# mcat-4cu-b-v2g.net
KiCad netlist of a schematic drawn in EAGLE
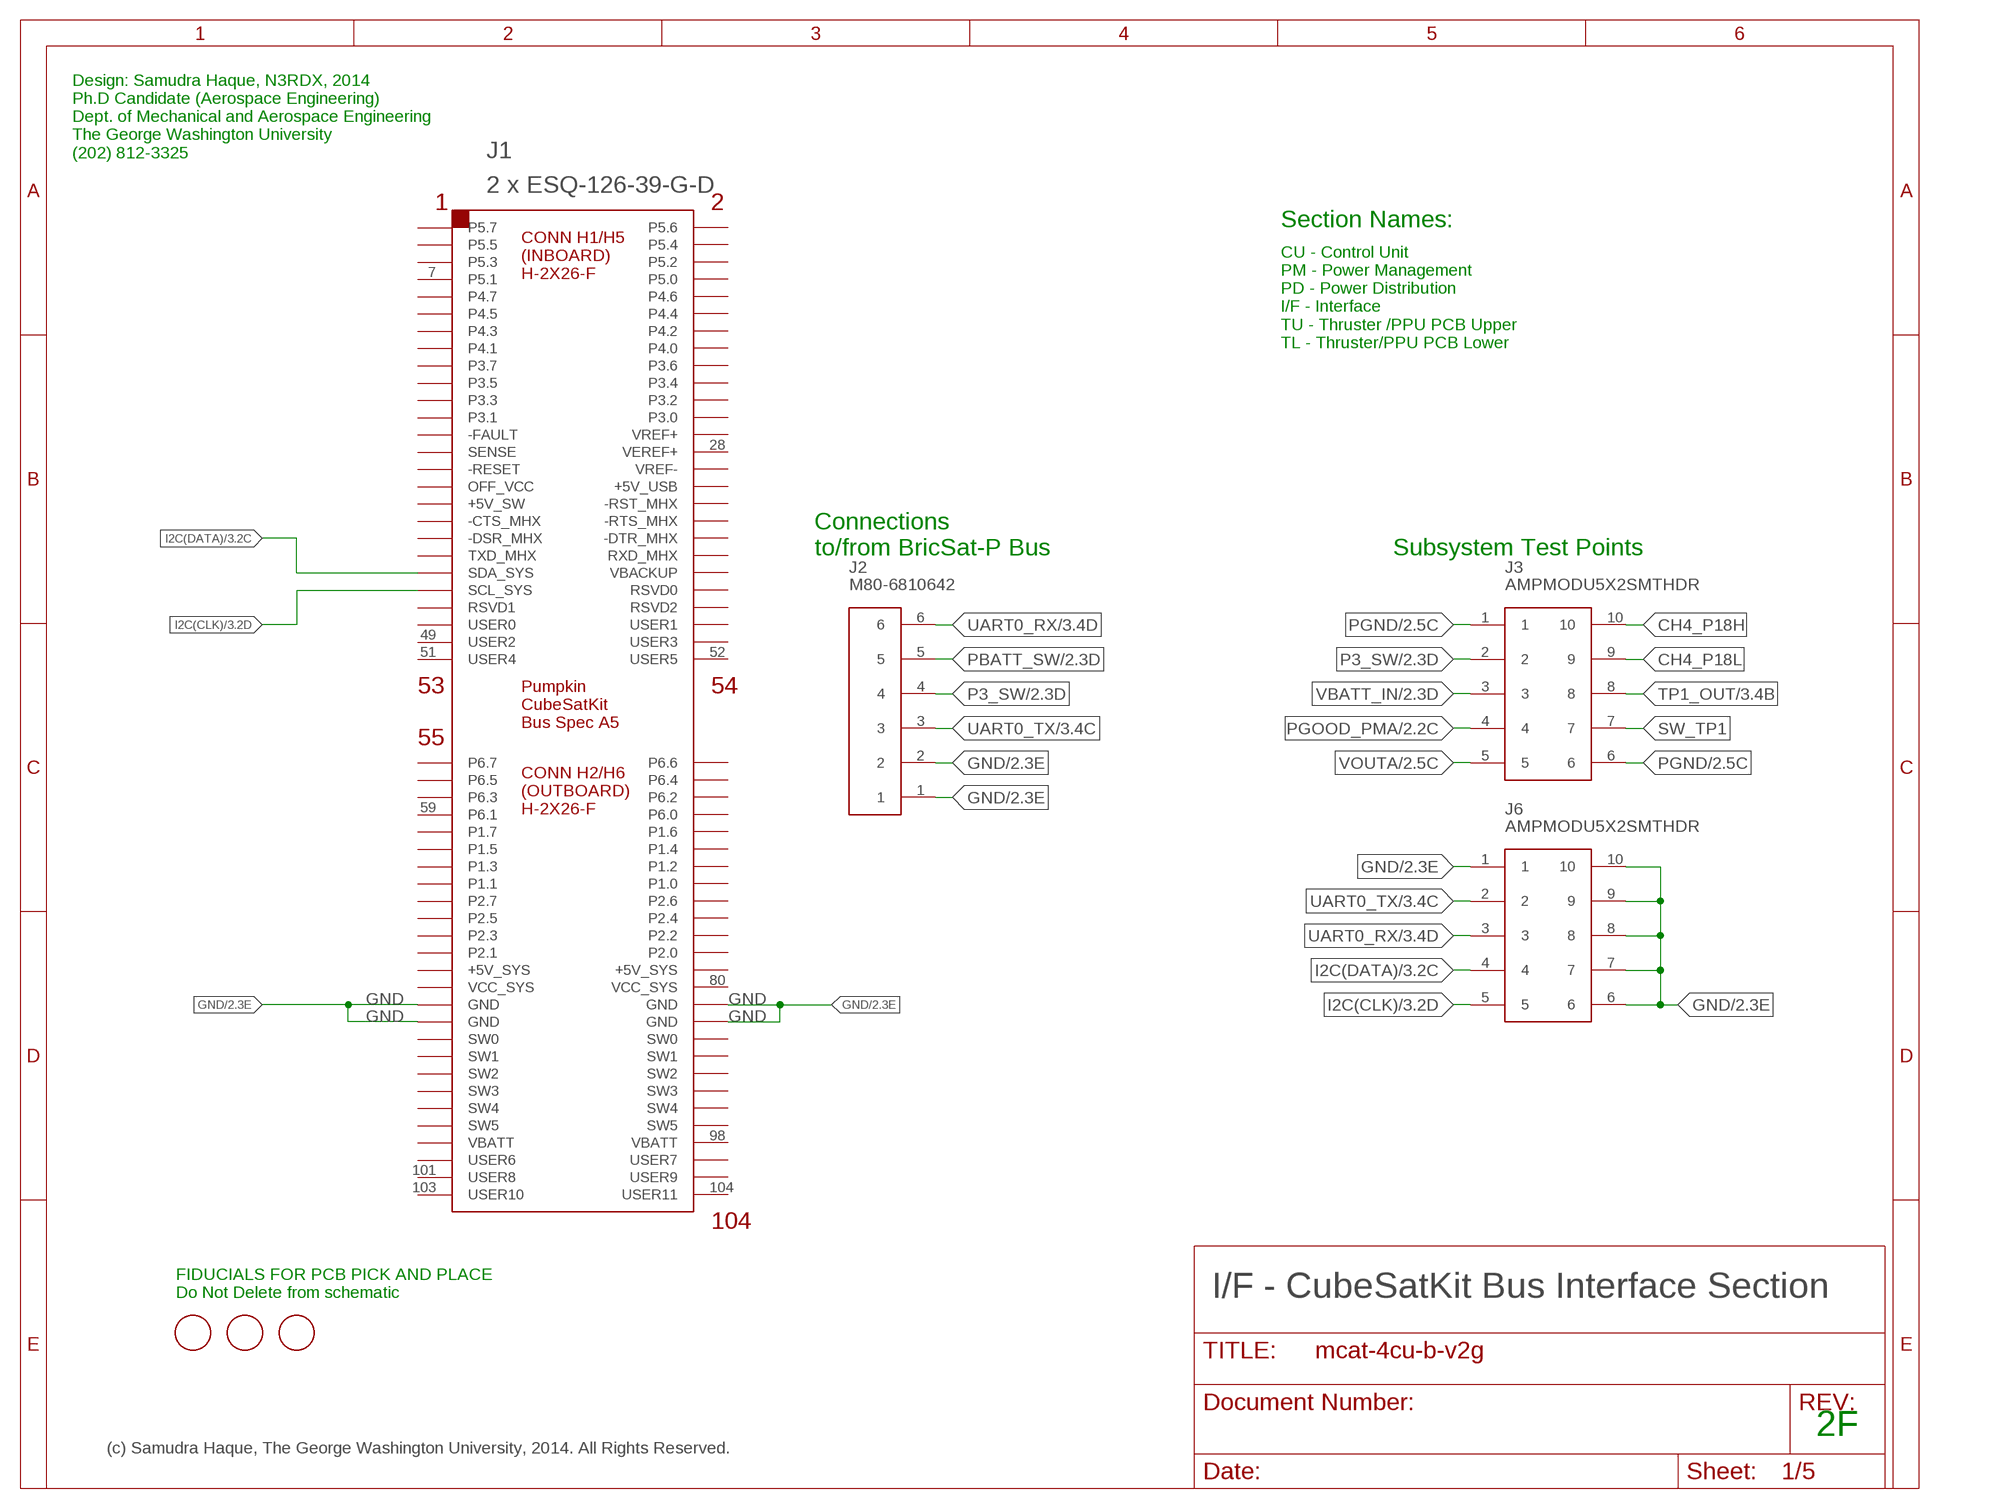
[diagram p0: schematic, sheet 1]
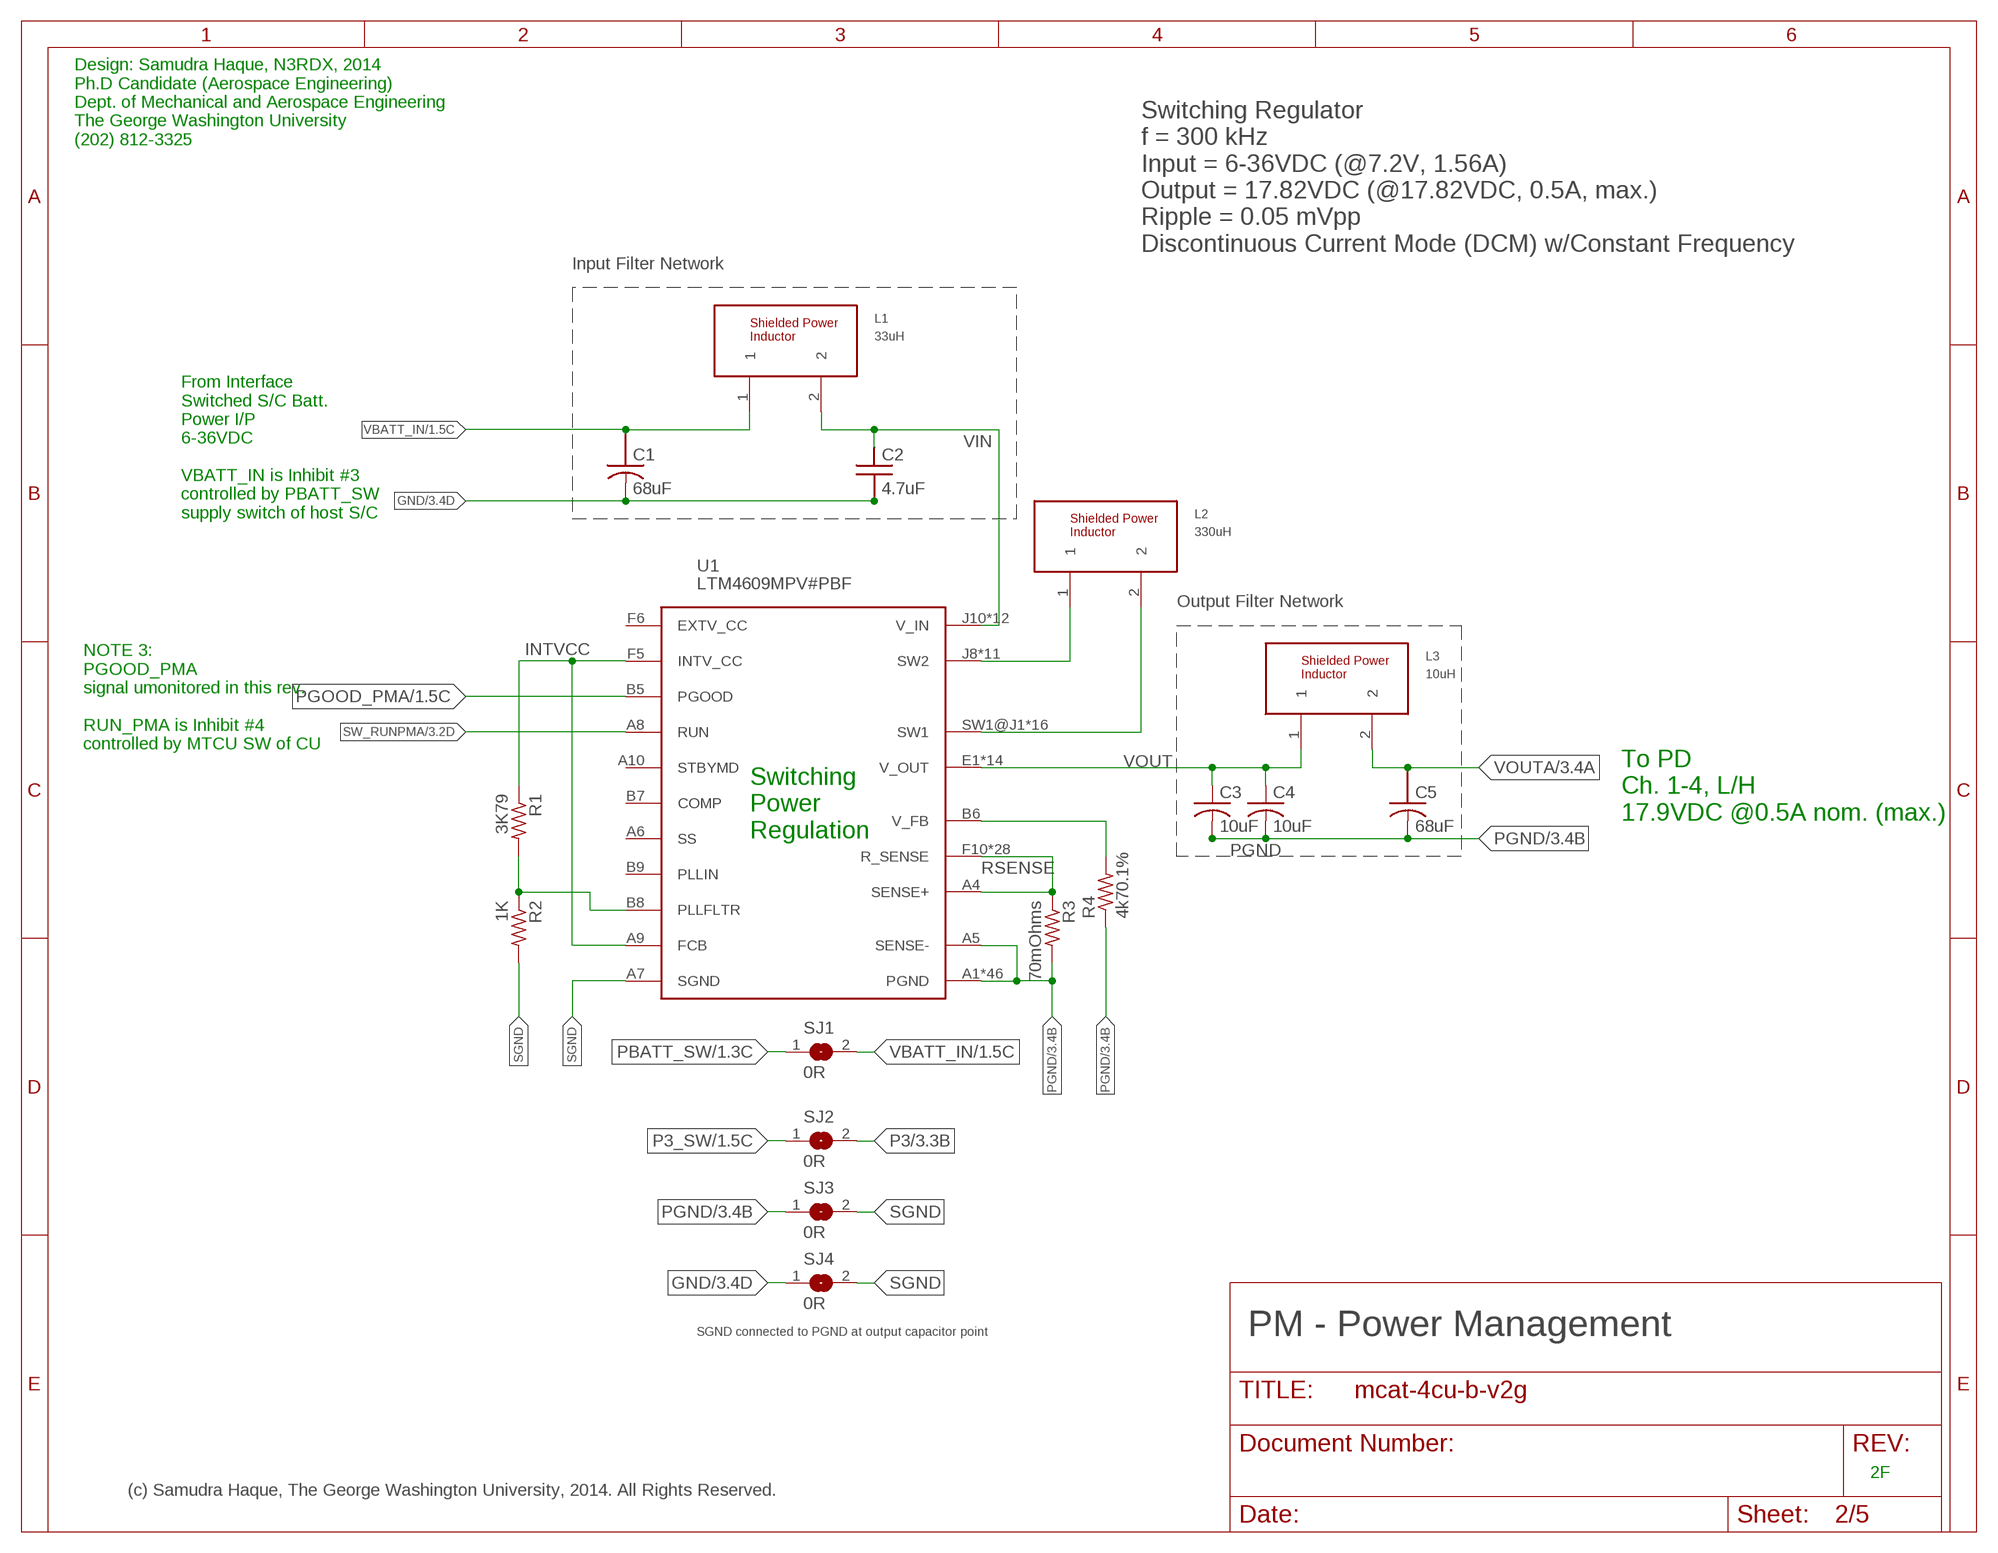
[diagram p1: schematic, sheet 2]
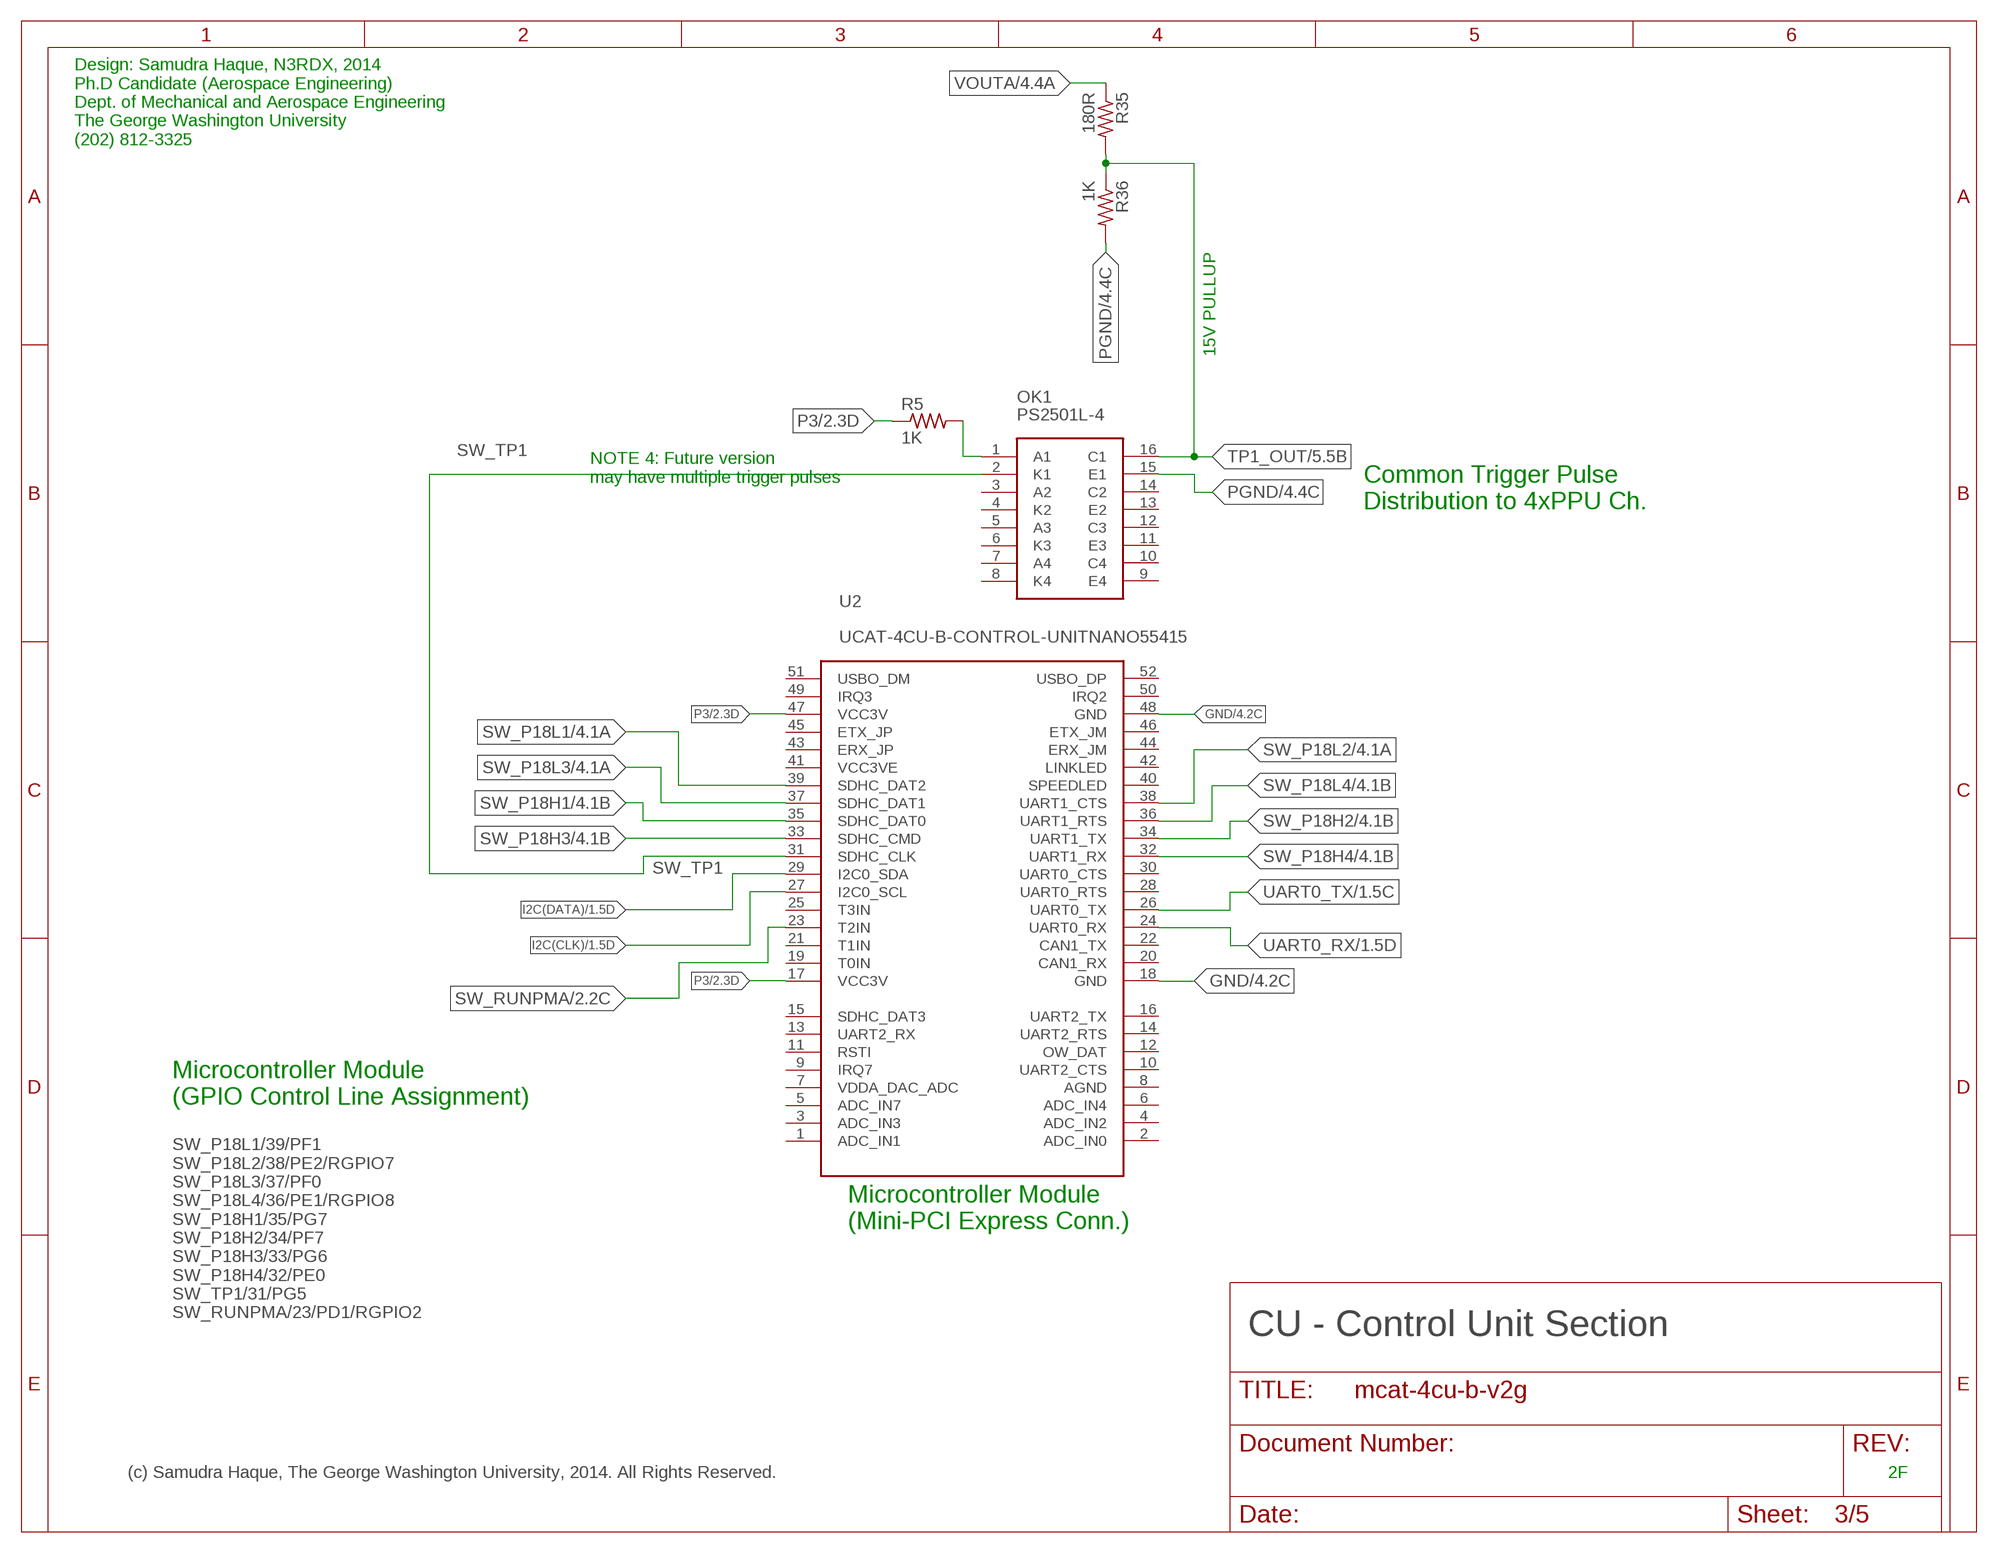
[diagram p2: schematic, sheet 3]
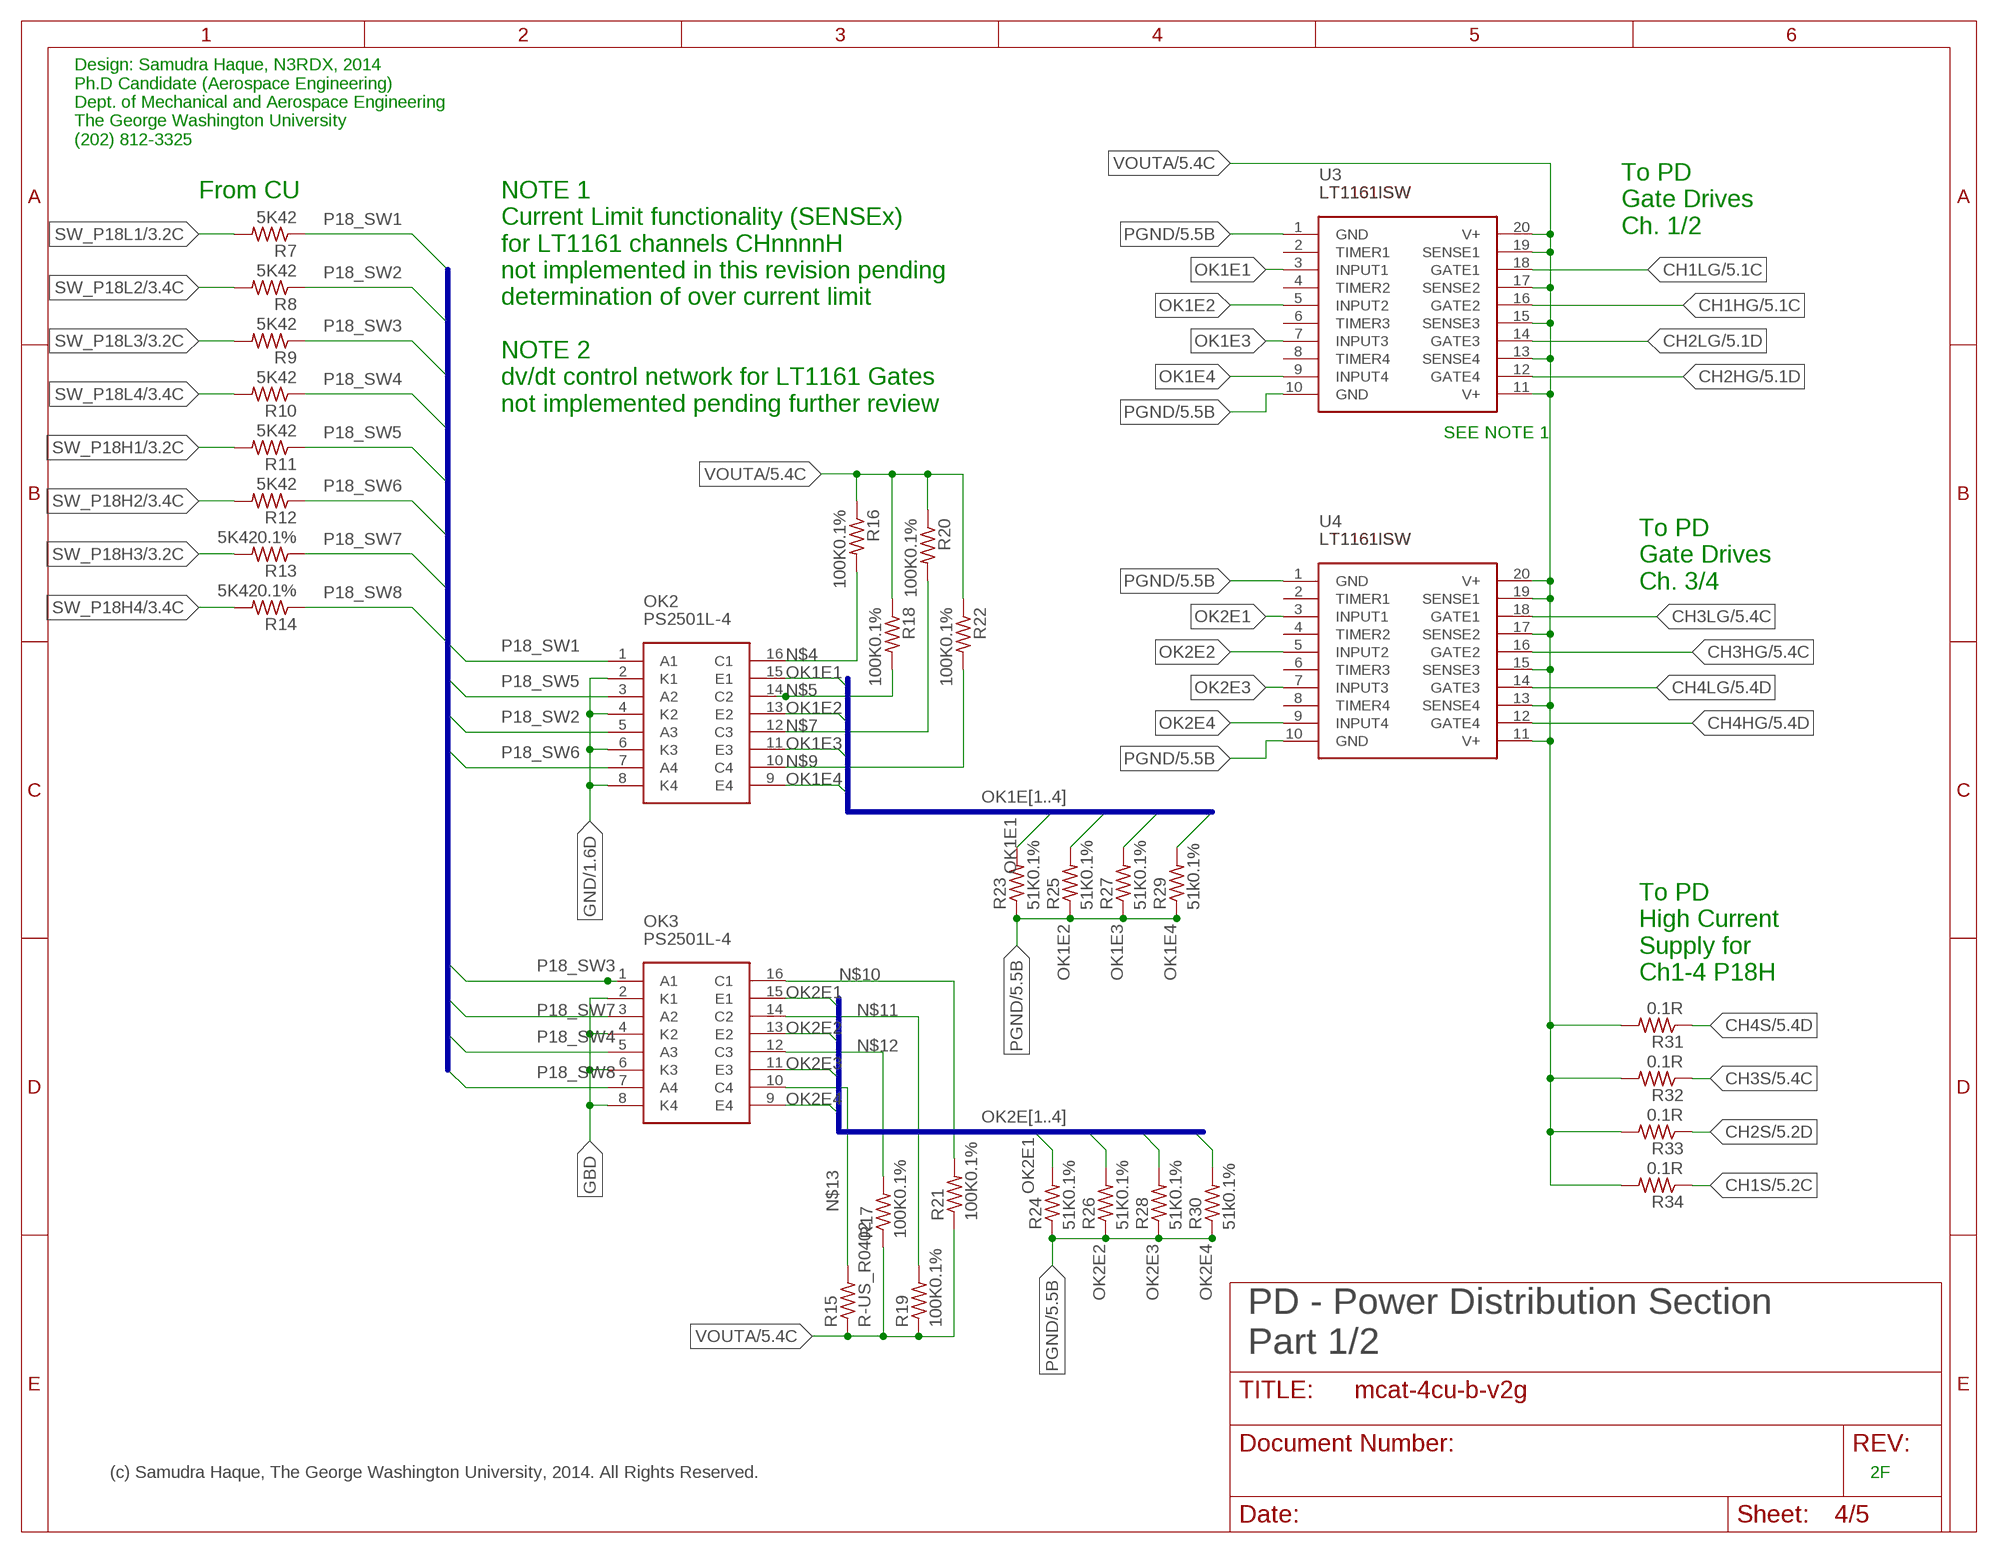
[diagram p3: schematic, sheet 4]
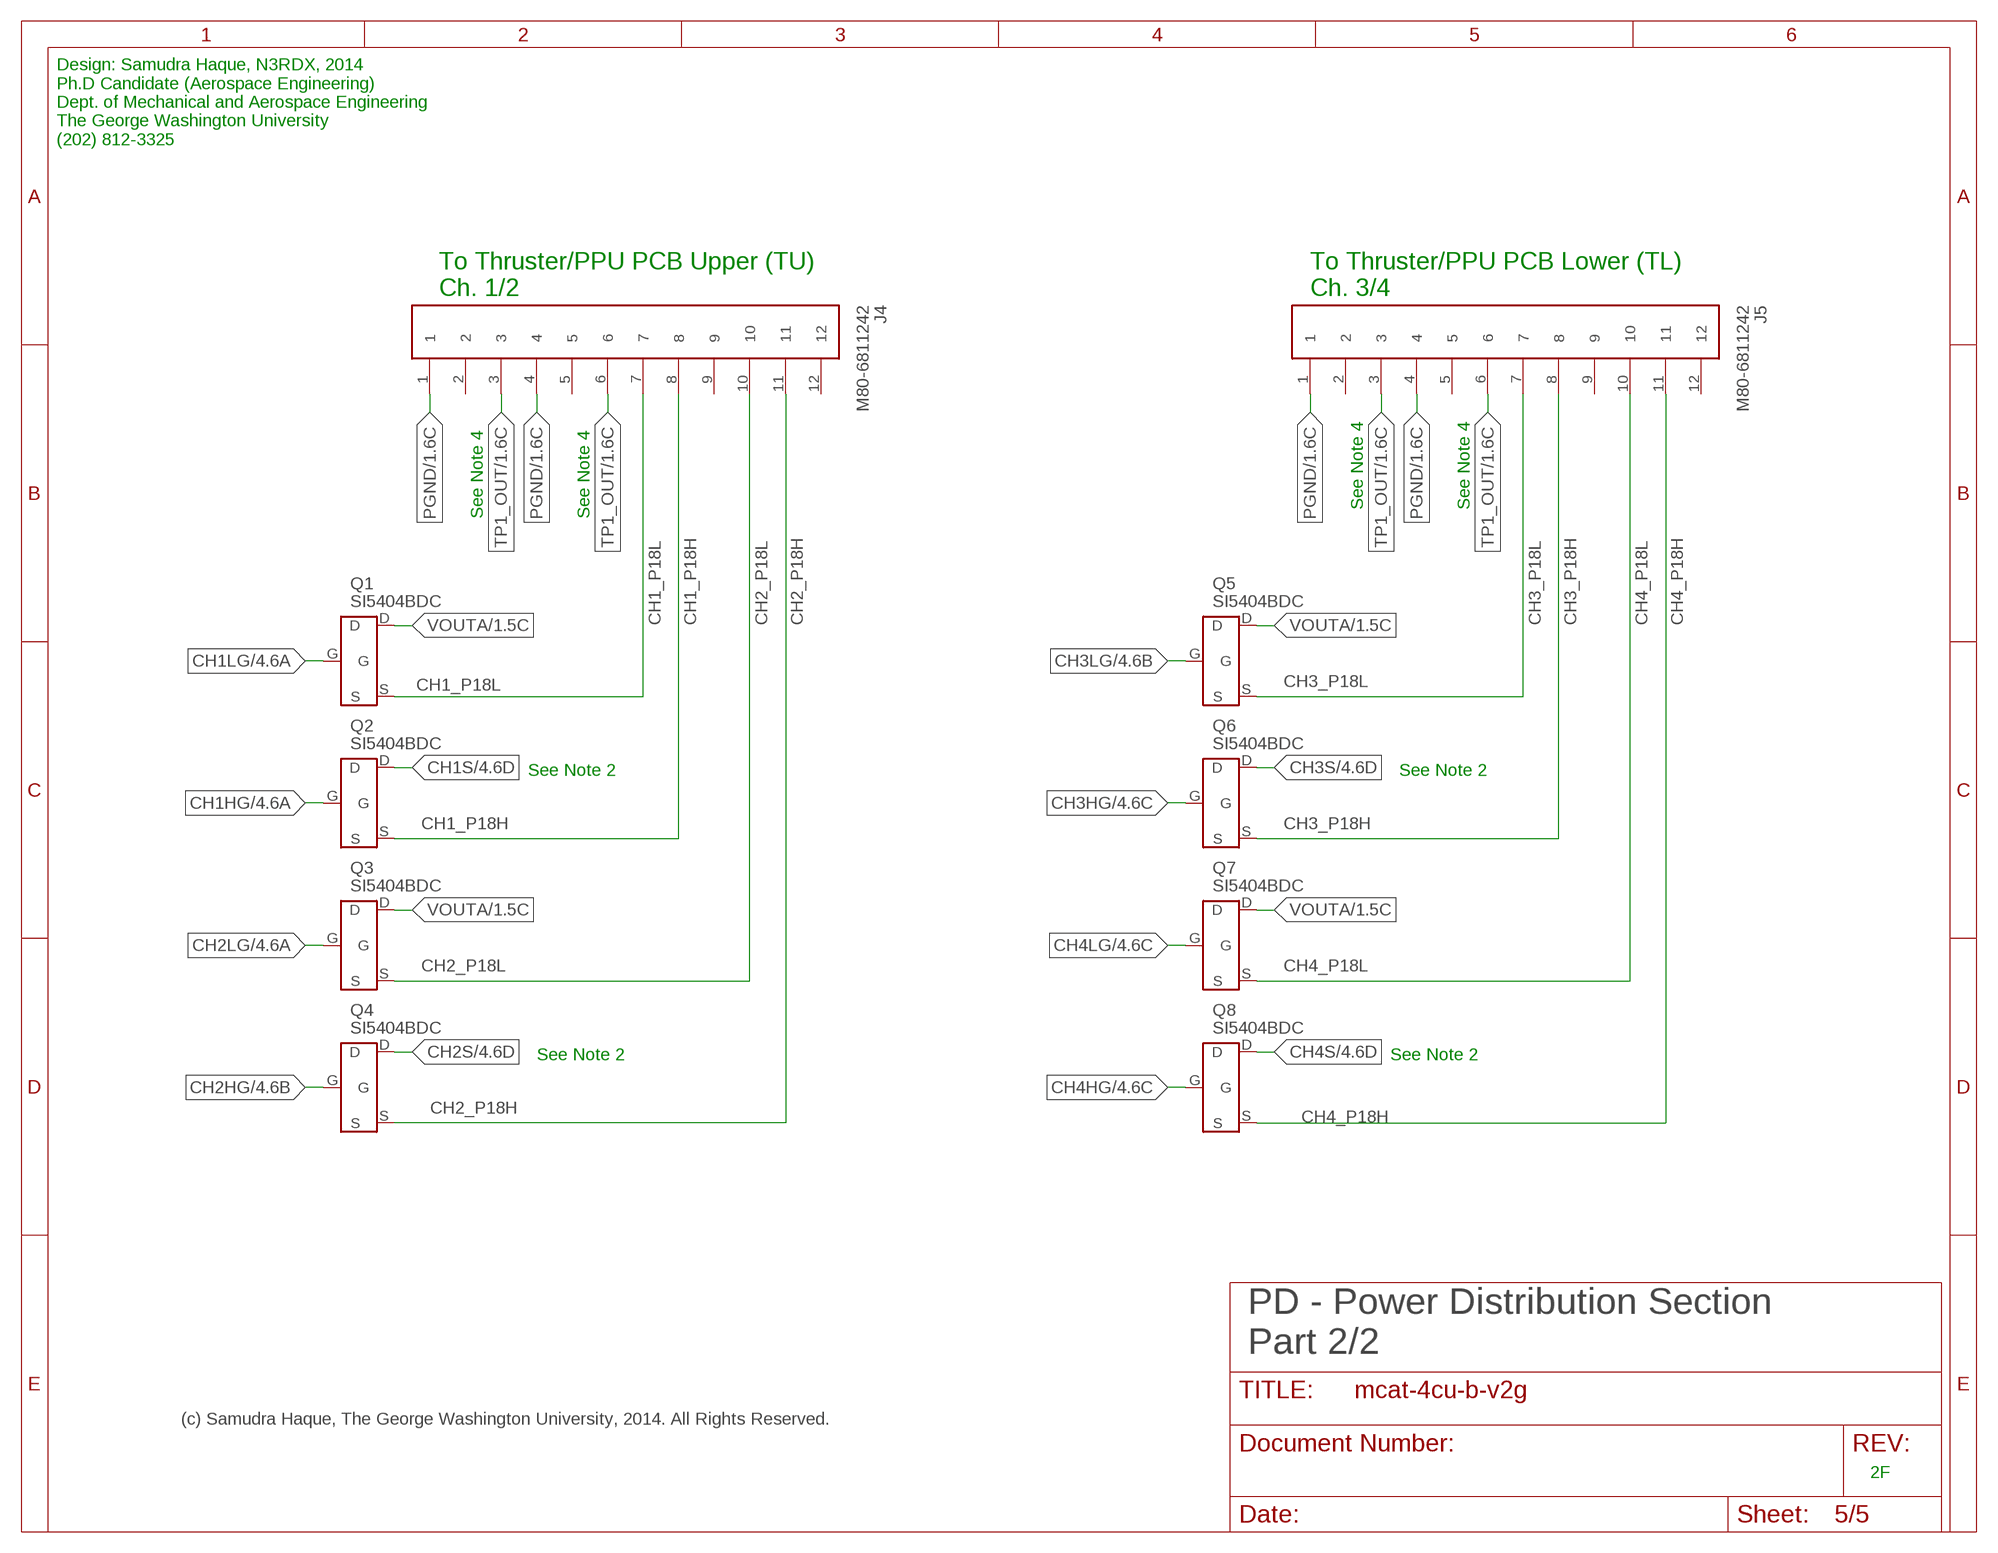
[diagram p4: schematic, sheet 5]

(export (version "E")
  (design (tool "Eeschema 10.0.6"))
  (components
    (comp (ref "C1")
      (value "68uF")
      (footprint "eagle-import:OS-CON-SVPF-F12")
      (libsource (lib "eagle-import") (part "OSCON-50SVPF68M"))
    )
    (comp (ref "C2")
      (value "4.7uF")
      (footprint "eagle-import:MLCC-X7R-1210")
      (libsource (lib "eagle-import") (part "AVX-LD105C475KAB2A"))
    )
    (comp (ref "C3")
      (value "10uF")
      (footprint "eagle-import:C1210K")
      (libsource (lib "eagle-import") (part "C-USC1210K"))
    )
    (comp (ref "C4")
      (value "10uF")
      (footprint "eagle-import:C1210K")
      (libsource (lib "eagle-import") (part "C-USC1210K"))
    )
    (comp (ref "C5")
      (value "68uF")
      (footprint "eagle-import:OS-CON-SVPF-F12")
      (libsource (lib "eagle-import") (part "OSCON-50SVPF68M"))
    )
    (comp (ref "L1")
      (value "33uH")
      (footprint "eagle-import:MSS1048")
      (libsource (lib "eagle-import") (part "MSS1038-333ML_"))
    )
    (comp (ref "L2")
      (value "330uH")
      (footprint "eagle-import:MSS1048")
      (libsource (lib "eagle-import") (part "MSS1048-334KL_"))
    )
    (comp (ref "L3")
      (value "10uH")
      (footprint "eagle-import:SERIES-POWER-INDUCTORS")
      (fields (field (name "MF") "PANASONIC") (field (name "MPN") "ELL5PS100M"))
      (libsource (lib "eagle-import") (part "ELL-5PS100M"))
    )
    (comp (ref "R1")
      (value "3K79")
      (footprint "eagle-import:R0805")
      (libsource (lib "eagle-import") (part "R-US_R0805"))
    )
    (comp (ref "R2")
      (value "1K")
      (footprint "eagle-import:R0805")
      (libsource (lib "eagle-import") (part "R-US_R0805"))
    )
    (comp (ref "R3")
      (value "70mOhms")
      (footprint "eagle-import:R1206")
      (libsource (lib "eagle-import") (part "resistor_R-US_R1206"))
    )
    (comp (ref "R4")
      (value "4k70.1%")
      (footprint "eagle-import:R0603")
      (libsource (lib "eagle-import") (part "resistor_R-US_R0603"))
    )
    (comp (ref "SJ1") (value "0R") (footprint "eagle-import:SJ") (libsource (lib "eagle-import") (part "SJ")))
    (comp (ref "SJ2") (value "0R") (footprint "eagle-import:SJ") (libsource (lib "eagle-import") (part "SJ")))
    (comp (ref "SJ3") (value "0R") (footprint "eagle-import:SJ") (libsource (lib "eagle-import") (part "SJ")))
    (comp (ref "SJ4") (value "0R") (footprint "eagle-import:SJ") (libsource (lib "eagle-import") (part "SJ")))
    (comp (ref "U1")
      (value "LTM4609MPV#PBF")
      (footprint "eagle-import:LGA-141-LTC-05-08-1840-B")
      (libsource (lib "eagle-import") (part "LTM4609MPV#PBFROHS/HITEMP"))
    )
    (comp (ref "OK1")
      (value "PS2501L-4")
      (footprint "eagle-import:PS2501L-4")
      (libsource (lib "eagle-import") (part "PS2501L-4"))
    )
    (comp (ref "R5")
      (value "1K")
      (footprint "eagle-import:R0805")
      (libsource (lib "eagle-import") (part "resistor_R-US_R0805"))
    )
    (comp (ref "R35")
      (value "180R")
      (footprint "eagle-import:R0805")
      (libsource (lib "eagle-import") (part "resistor_R-US_R0805"))
    )
    (comp (ref "R36")
      (value "1K")
      (footprint "eagle-import:R0805")
      (libsource (lib "eagle-import") (part "resistor_R-US_R0805"))
    )
    (comp (ref "U2")
      (value "UCAT-4CU-B-CONTROL-UNITNANO55415")
      (footprint "eagle-import:MOLEX-MINI-PCI-EXPRESS-8MM-52CKT")
      (libsource (lib "eagle-import") (part "UCAT-4CU-B-CONTROL-UNITNANO55415"))
    )
    (comp (ref "J4")
      (value "M80-6811242")
      (footprint "eagle-import:M80-68112")
      (libsource (lib "eagle-import") (part "M80-6811242"))
    )
    (comp (ref "J5")
      (value "M80-6811242")
      (footprint "eagle-import:M80-68112")
      (libsource (lib "eagle-import") (part "M80-6811242"))
    )
    (comp (ref "Q1")
      (value "SI5404BDC")
      (footprint "eagle-import:1206-8-CHIPFET")
      (libsource (lib "eagle-import") (part "SI5404BDC"))
    )
    (comp (ref "Q2")
      (value "SI5404BDC")
      (footprint "eagle-import:1206-8-CHIPFET")
      (libsource (lib "eagle-import") (part "SI5404BDC"))
    )
    (comp (ref "Q3")
      (value "SI5404BDC")
      (footprint "eagle-import:1206-8-CHIPFET")
      (libsource (lib "eagle-import") (part "SI5404BDC"))
    )
    (comp (ref "Q4")
      (value "SI5404BDC")
      (footprint "eagle-import:1206-8-CHIPFET")
      (libsource (lib "eagle-import") (part "SI5404BDC"))
    )
    (comp (ref "Q5")
      (value "SI5404BDC")
      (footprint "eagle-import:1206-8-CHIPFET")
      (libsource (lib "eagle-import") (part "SI5404BDC"))
    )
    (comp (ref "Q6")
      (value "SI5404BDC")
      (footprint "eagle-import:1206-8-CHIPFET")
      (libsource (lib "eagle-import") (part "SI5404BDC"))
    )
    (comp (ref "Q7")
      (value "SI5404BDC")
      (footprint "eagle-import:1206-8-CHIPFET")
      (libsource (lib "eagle-import") (part "SI5404BDC"))
    )
    (comp (ref "Q8")
      (value "SI5404BDC")
      (footprint "eagle-import:1206-8-CHIPFET")
      (libsource (lib "eagle-import") (part "SI5404BDC"))
    )
    (comp (ref "FID1")
      (value "FIDUCIAL")
      (footprint "eagle-import:FIDUCIAL_1MM")
      (libsource (lib "eagle-import") (part "FIDUCIAL"))
    )
    (comp (ref "FID2")
      (value "FIDUCIAL")
      (footprint "eagle-import:FIDUCIAL_1MM")
      (libsource (lib "eagle-import") (part "FIDUCIAL"))
    )
    (comp (ref "FID3")
      (value "FIDUCIAL")
      (footprint "eagle-import:FIDUCIAL_1MM")
      (libsource (lib "eagle-import") (part "FIDUCIAL"))
    )
    (comp (ref "J1")
      (value "2 x ESQ-126-39-G-D")
      (footprint "eagle-import:CSK-BUS-PKG")
      (libsource (lib "eagle-import") (part "CSK-BUS-CONN2X2X26"))
    )
    (comp (ref "J2")
      (value "M80-6810642")
      (footprint "eagle-import:M80-68106")
      (libsource (lib "eagle-import") (part "M80-6810642"))
    )
    (comp (ref "J3")
      (value "AMPMODU5X2SMTHDR")
      (footprint "eagle-import:AMPMODU-SMT-PIN-HEADER-5X2")
      (libsource (lib "eagle-import") (part "AMPMODU-5-146131-X(5X2)"))
    )
    (comp (ref "J6")
      (value "AMPMODU5X2SMTHDR")
      (footprint "eagle-import:AMPMODU-SMT-PIN-HEADER-5X2")
      (libsource (lib "eagle-import") (part "AMPMODU-5-146131-X(5X2)"))
    )
    (comp (ref "OK2")
      (value "PS2501L-4")
      (footprint "eagle-import:PS2501L-4")
      (libsource (lib "eagle-import") (part "PS2501L-4"))
    )
    (comp (ref "OK3")
      (value "PS2501L-4")
      (footprint "eagle-import:PS2501L-4")
      (libsource (lib "eagle-import") (part "PS2501L-4"))
    )
    (comp (ref "R7")
      (value "5K42")
      (footprint "eagle-import:R1206")
      (libsource (lib "eagle-import") (part "resistor_R-US_R1206"))
    )
    (comp (ref "R8")
      (value "5K42")
      (footprint "eagle-import:R1206")
      (libsource (lib "eagle-import") (part "resistor_R-US_R1206"))
    )
    (comp (ref "R9")
      (value "5K42")
      (footprint "eagle-import:R1206")
      (libsource (lib "eagle-import") (part "resistor_R-US_R1206"))
    )
    (comp (ref "R10")
      (value "5K42")
      (footprint "eagle-import:R1206")
      (libsource (lib "eagle-import") (part "resistor_R-US_R1206"))
    )
    (comp (ref "R11")
      (value "5K42")
      (footprint "eagle-import:R1206")
      (libsource (lib "eagle-import") (part "resistor_R-US_R1206"))
    )
    (comp (ref "R12")
      (value "5K42")
      (footprint "eagle-import:R1206")
      (libsource (lib "eagle-import") (part "resistor_R-US_R1206"))
    )
    (comp (ref "R13")
      (value "5K420.1%")
      (footprint "eagle-import:R1206")
      (libsource (lib "eagle-import") (part "resistor_R-US_R1206"))
    )
    (comp (ref "R14")
      (value "5K420.1%")
      (footprint "eagle-import:R1206")
      (libsource (lib "eagle-import") (part "resistor_R-US_R1206"))
    )
    (comp (ref "R15")
      (value "R-US_R0402")
      (footprint "eagle-import:R0402")
      (libsource (lib "eagle-import") (part "resistor_R-US_R0402"))
    )
    (comp (ref "R16")
      (value "100K0.1%")
      (footprint "eagle-import:R0402")
      (libsource (lib "eagle-import") (part "resistor_R-US_R0402"))
    )
    (comp (ref "R17")
      (value "100K0.1%")
      (footprint "eagle-import:R0402")
      (libsource (lib "eagle-import") (part "resistor_R-US_R0402"))
    )
    (comp (ref "R18")
      (value "100K0.1%")
      (footprint "eagle-import:R0402")
      (libsource (lib "eagle-import") (part "resistor_R-US_R0402"))
    )
    (comp (ref "R19")
      (value "100K0.1%")
      (footprint "eagle-import:R0402")
      (libsource (lib "eagle-import") (part "resistor_R-US_R0402"))
    )
    (comp (ref "R20")
      (value "100K0.1%")
      (footprint "eagle-import:R0402")
      (libsource (lib "eagle-import") (part "resistor_R-US_R0402"))
    )
    (comp (ref "R21")
      (value "100K0.1%")
      (footprint "eagle-import:R0402")
      (libsource (lib "eagle-import") (part "resistor_R-US_R0402"))
    )
    (comp (ref "R22")
      (value "100K0.1%")
      (footprint "eagle-import:R0402")
      (libsource (lib "eagle-import") (part "resistor_R-US_R0402"))
    )
    (comp (ref "R23")
      (value "51K0.1%")
      (footprint "eagle-import:R0603")
      (libsource (lib "eagle-import") (part "resistor_R-US_R0603"))
    )
    (comp (ref "R24")
      (value "51K0.1%")
      (footprint "eagle-import:R0603")
      (libsource (lib "eagle-import") (part "resistor_R-US_R0603"))
    )
    (comp (ref "R25")
      (value "51K0.1%")
      (footprint "eagle-import:R0603")
      (libsource (lib "eagle-import") (part "resistor_R-US_R0603"))
    )
    (comp (ref "R26")
      (value "51K0.1%")
      (footprint "eagle-import:R0603")
      (libsource (lib "eagle-import") (part "resistor_R-US_R0603"))
    )
    (comp (ref "R27")
      (value "51K0.1%")
      (footprint "eagle-import:R0603")
      (libsource (lib "eagle-import") (part "resistor_R-US_R0603"))
    )
    (comp (ref "R28")
      (value "51K0.1%")
      (footprint "eagle-import:R0603")
      (libsource (lib "eagle-import") (part "resistor_R-US_R0603"))
    )
    (comp (ref "R29")
      (value "51k0.1%")
      (footprint "eagle-import:R0603")
      (libsource (lib "eagle-import") (part "resistor_R-US_R0603"))
    )
    (comp (ref "R30")
      (value "51k0.1%")
      (footprint "eagle-import:R0603")
      (libsource (lib "eagle-import") (part "resistor_R-US_R0603"))
    )
    (comp (ref "R31")
      (value "0.1R")
      (footprint "eagle-import:R0402")
      (libsource (lib "eagle-import") (part "R-US_R0402"))
    )
    (comp (ref "R32")
      (value "0.1R")
      (footprint "eagle-import:R0402")
      (libsource (lib "eagle-import") (part "R-US_R0402"))
    )
    (comp (ref "R33")
      (value "0.1R")
      (footprint "eagle-import:R0402")
      (libsource (lib "eagle-import") (part "R-US_R0402"))
    )
    (comp (ref "R34")
      (value "0.1R")
      (footprint "eagle-import:R0402")
      (libsource (lib "eagle-import") (part "R-US_R0402"))
    )
    (comp (ref "U3")
      (value "LT1161ISW")
      (footprint "eagle-import:20-LEAD-PLASTIC-SO")
      (libsource (lib "eagle-import") (part "LT1161ISW"))
    )
    (comp (ref "U4")
      (value "LT1161ISW")
      (footprint "eagle-import:20-LEAD-PLASTIC-SO")
      (libsource (lib "eagle-import") (part "LT1161ISW"))
    )
  )
  (nets
    (net (code "3") (name "CH1HG") (class "Default")
      (node (ref "Q2") (pin "G") (pinfunction "G_G") (pintype "bidirectional"))
      (node (ref "U3") (pin "16") (pinfunction "GATE2_16") (pintype "bidirectional"))
    )
    (net (code "4") (name "CH1LG") (class "Default")
      (node (ref "Q1") (pin "G") (pinfunction "G_G") (pintype "bidirectional"))
      (node (ref "U3") (pin "18") (pinfunction "GATE1_18") (pintype "bidirectional"))
    )
    (net (code "5") (name "CH1S") (class "Default")
      (node (ref "Q2") (pin "D") (pinfunction "D_D") (pintype "bidirectional"))
      (node (ref "R34") (pin "1") (pinfunction "1_1") (pintype "passive"))
    )
    (net (code "6") (name "CH1_P18H") (class "Default")
      (node (ref "J4") (pin "8") (pinfunction "8_8") (pintype "bidirectional"))
      (node (ref "Q2") (pin "S") (pinfunction "S_S") (pintype "bidirectional"))
    )
    (net (code "7") (name "CH1_P18L") (class "Default")
      (node (ref "J4") (pin "7") (pinfunction "7_7") (pintype "bidirectional"))
      (node (ref "Q1") (pin "S") (pinfunction "S_S") (pintype "bidirectional"))
    )
    (net (code "8") (name "CH2HG") (class "Default")
      (node (ref "Q4") (pin "G") (pinfunction "G_G") (pintype "bidirectional"))
      (node (ref "U3") (pin "12") (pinfunction "GATE4_12") (pintype "bidirectional"))
    )
    (net (code "9") (name "CH2LG") (class "Default")
      (node (ref "Q3") (pin "G") (pinfunction "G_G") (pintype "bidirectional"))
      (node (ref "U3") (pin "14") (pinfunction "GATE3_14") (pintype "bidirectional"))
    )
    (net (code "10") (name "CH2S") (class "Default")
      (node (ref "Q4") (pin "D") (pinfunction "D_D") (pintype "bidirectional"))
      (node (ref "R33") (pin "1") (pinfunction "1_1") (pintype "passive"))
    )
    (net (code "11") (name "CH2_P18H") (class "Default")
      (node (ref "J4") (pin "11") (pinfunction "11_11") (pintype "bidirectional"))
      (node (ref "Q4") (pin "S") (pinfunction "S_S") (pintype "bidirectional"))
    )
    (net (code "12") (name "CH2_P18L") (class "Default")
      (node (ref "J4") (pin "10") (pinfunction "10_10") (pintype "bidirectional"))
      (node (ref "Q3") (pin "S") (pinfunction "S_S") (pintype "bidirectional"))
    )
    (net (code "13") (name "CH3HG") (class "Default")
      (node (ref "Q6") (pin "G") (pinfunction "G_G") (pintype "bidirectional"))
      (node (ref "U4") (pin "16") (pinfunction "GATE2_16") (pintype "bidirectional"))
    )
    (net (code "14") (name "CH3LG") (class "Default")
      (node (ref "Q5") (pin "G") (pinfunction "G_G") (pintype "bidirectional"))
      (node (ref "U4") (pin "18") (pinfunction "GATE1_18") (pintype "bidirectional"))
    )
    (net (code "15") (name "CH3S") (class "Default")
      (node (ref "Q6") (pin "D") (pinfunction "D_D") (pintype "bidirectional"))
      (node (ref "R32") (pin "1") (pinfunction "1_1") (pintype "passive"))
    )
    (net (code "16") (name "CH3_P18H") (class "Default")
      (node (ref "J5") (pin "8") (pinfunction "8_8") (pintype "bidirectional"))
      (node (ref "Q6") (pin "S") (pinfunction "S_S") (pintype "bidirectional"))
    )
    (net (code "17") (name "CH3_P18L") (class "Default")
      (node (ref "J5") (pin "7") (pinfunction "7_7") (pintype "bidirectional"))
      (node (ref "Q5") (pin "S") (pinfunction "S_S") (pintype "bidirectional"))
    )
    (net (code "18") (name "CH4HG") (class "Default")
      (node (ref "Q8") (pin "G") (pinfunction "G_G") (pintype "bidirectional"))
      (node (ref "U4") (pin "12") (pinfunction "GATE4_12") (pintype "bidirectional"))
    )
    (net (code "19") (name "CH4LG") (class "Default")
      (node (ref "Q7") (pin "G") (pinfunction "G_G") (pintype "bidirectional"))
      (node (ref "U4") (pin "14") (pinfunction "GATE3_14") (pintype "bidirectional"))
    )
    (net (code "20") (name "CH4S") (class "Default")
      (node (ref "Q8") (pin "D") (pinfunction "D_D") (pintype "bidirectional"))
      (node (ref "R31") (pin "1") (pinfunction "1_1") (pintype "passive"))
    )
    (net (code "21") (name "CH4_P18H") (class "Default")
      (node (ref "J3") (pin "10") (pinfunction "10_10") (pintype "bidirectional"))
      (node (ref "J5") (pin "11") (pinfunction "11_11") (pintype "bidirectional"))
      (node (ref "Q8") (pin "S") (pinfunction "S_S") (pintype "bidirectional"))
    )
    (net (code "22") (name "CH4_P18L") (class "Default")
      (node (ref "J3") (pin "9") (pinfunction "9_9") (pintype "bidirectional"))
      (node (ref "J5") (pin "10") (pinfunction "10_10") (pintype "bidirectional"))
      (node (ref "Q7") (pin "S") (pinfunction "S_S") (pintype "bidirectional"))
    )
    (net (code "23") (name "GBD") (class "Default")
      (node (ref "OK3") (pin "2") (pinfunction "K1_2") (pintype "bidirectional"))
      (node (ref "OK3") (pin "4") (pinfunction "K2_4") (pintype "bidirectional"))
      (node (ref "OK3") (pin "6") (pinfunction "K3_6") (pintype "bidirectional"))
      (node (ref "OK3") (pin "8") (pinfunction "K4_8") (pintype "bidirectional"))
    )
    (net (code "24") (name "GND") (class "Default")
      (node (ref "C1") (pin "K1") (pinfunction "K_K1") (pintype "passive"))
      (node (ref "C2") (pin "2") (pinfunction "2_2") (pintype "passive"))
      (node (ref "J1") (pin "81") (pinfunction "GND_81") (pintype "bidirectional"))
      (node (ref "J1") (pin "82") (pinfunction "GND_82") (pintype "bidirectional"))
      (node (ref "J1") (pin "83") (pinfunction "GND_83") (pintype "bidirectional"))
      (node (ref "J1") (pin "84") (pinfunction "GND_84") (pintype "bidirectional"))
      (node (ref "J2") (pin "1") (pinfunction "1_1") (pintype "bidirectional"))
      (node (ref "J2") (pin "2") (pinfunction "2_2") (pintype "bidirectional"))
      (node (ref "J6") (pin "1") (pinfunction "1_1") (pintype "bidirectional"))
      (node (ref "J6") (pin "10") (pinfunction "10_10") (pintype "bidirectional"))
      (node (ref "J6") (pin "6") (pinfunction "6_6") (pintype "bidirectional"))
      (node (ref "J6") (pin "7") (pinfunction "7_7") (pintype "bidirectional"))
      (node (ref "J6") (pin "8") (pinfunction "8_8") (pintype "bidirectional"))
      (node (ref "J6") (pin "9") (pinfunction "9_9") (pintype "bidirectional"))
      (node (ref "OK2") (pin "2") (pinfunction "K1_2") (pintype "bidirectional"))
      (node (ref "OK2") (pin "4") (pinfunction "K2_4") (pintype "bidirectional"))
      (node (ref "OK2") (pin "6") (pinfunction "K3_6") (pintype "bidirectional"))
      (node (ref "OK2") (pin "8") (pinfunction "K4_8") (pintype "bidirectional"))
      (node (ref "SJ4") (pin "1") (pinfunction "1_1") (pintype "passive"))
      (node (ref "U2") (pin "18") (pinfunction "GND_18") (pintype "bidirectional"))
      (node (ref "U2") (pin "48") (pinfunction "GND_48") (pintype "bidirectional"))
    )
    (net (code "25") (name "I2C(CLK)") (class "Default")
      (node (ref "J1") (pin "43") (pinfunction "SCL_SYS_43") (pintype "bidirectional"))
      (node (ref "J6") (pin "5") (pinfunction "5_5") (pintype "bidirectional"))
      (node (ref "U2") (pin "27") (pinfunction "I2C0_SCL_27") (pintype "bidirectional"))
    )
    (net (code "26") (name "I2C(DATA)") (class "Default")
      (node (ref "J1") (pin "41") (pinfunction "SDA_SYS_41") (pintype "bidirectional"))
      (node (ref "J6") (pin "4") (pinfunction "4_4") (pintype "bidirectional"))
      (node (ref "U2") (pin "29") (pinfunction "I2C0_SDA_29") (pintype "bidirectional"))
    )
    (net (code "27") (name "INTVCC") (class "Default")
      (node (ref "R1") (pin "1") (pinfunction "1_1") (pintype "passive"))
      (node (ref "U1") (pin "A9") (pinfunction "FCB_A9") (pintype "bidirectional"))
      (node (ref "U1") (pin "F5") (pinfunction "INTV_CC_F5") (pintype "bidirectional"))
    )
    (net (code "28") (name "N$4") (class "Default")
      (node (ref "OK2") (pin "16") (pinfunction "C1_16") (pintype "bidirectional"))
      (node (ref "R16") (pin "2") (pinfunction "2_2") (pintype "passive"))
    )
    (net (code "29") (name "N$5") (class "Default")
      (node (ref "OK2") (pin "14") (pinfunction "C2_14") (pintype "bidirectional"))
      (node (ref "R18") (pin "2") (pinfunction "2_2") (pintype "passive"))
    )
    (net (code "30") (name "N$7") (class "Default")
      (node (ref "OK2") (pin "12") (pinfunction "C3_12") (pintype "bidirectional"))
      (node (ref "R20") (pin "2") (pinfunction "2_2") (pintype "passive"))
    )
    (net (code "31") (name "N$9") (class "Default")
      (node (ref "OK2") (pin "10") (pinfunction "C4_10") (pintype "bidirectional"))
      (node (ref "R22") (pin "2") (pinfunction "2_2") (pintype "passive"))
    )
    (net (code "32") (name "N$10") (class "Default")
      (node (ref "OK3") (pin "16") (pinfunction "C1_16") (pintype "bidirectional"))
      (node (ref "R21") (pin "2") (pinfunction "2_2") (pintype "passive"))
    )
    (net (code "33") (name "N$11") (class "Default")
      (node (ref "OK3") (pin "14") (pinfunction "C2_14") (pintype "bidirectional"))
      (node (ref "R19") (pin "2") (pinfunction "2_2") (pintype "passive"))
    )
    (net (code "34") (name "N$12") (class "Default")
      (node (ref "OK3") (pin "12") (pinfunction "C3_12") (pintype "bidirectional"))
      (node (ref "R17") (pin "2") (pinfunction "2_2") (pintype "passive"))
    )
    (net (code "35") (name "N$13") (class "Default")
      (node (ref "OK3") (pin "10") (pinfunction "C4_10") (pintype "bidirectional"))
      (node (ref "R15") (pin "2") (pinfunction "2_2") (pintype "passive"))
    )
    (net (code "36") (name "Net-(L2-Pad1)") (class "Default")
      (node (ref "L2") (pin "1") (pinfunction "1_1") (pintype "bidirectional"))
      (node (ref "U1") (pin "J8") (pinfunction "SW2_J8") (pintype "bidirectional"))
      (node (ref "U1") (pin "J9") (pinfunction "SW2_J9") (pintype "bidirectional"))
      (node (ref "U1") (pin "K7") (pinfunction "SW2_K7") (pintype "bidirectional"))
      (node (ref "U1") (pin "K8") (pinfunction "SW2_K8") (pintype "bidirectional"))
      (node (ref "U1") (pin "K9") (pinfunction "SW2_K9") (pintype "bidirectional"))
      (node (ref "U1") (pin "L7") (pinfunction "SW2_L7") (pintype "bidirectional"))
      (node (ref "U1") (pin "L8") (pinfunction "SW2_L8") (pintype "bidirectional"))
      (node (ref "U1") (pin "L9") (pinfunction "SW2_L9") (pintype "bidirectional"))
      (node (ref "U1") (pin "M7") (pinfunction "SW2_M7") (pintype "bidirectional"))
      (node (ref "U1") (pin "M8") (pinfunction "SW2_M8") (pintype "bidirectional"))
      (node (ref "U1") (pin "M9") (pinfunction "SW2_M9") (pintype "bidirectional"))
    )
    (net (code "37") (name "Net-(L2-Pad2)") (class "Default")
      (node (ref "L2") (pin "2") (pinfunction "2_2") (pintype "bidirectional"))
      (node (ref "U1") (pin "SW1@J1") (pinfunction "SW1_SW1@J1") (pintype "bidirectional"))
      (node (ref "U1") (pin "SW1@J2") (pinfunction "SW1_SW1@J2") (pintype "bidirectional"))
      (node (ref "U1") (pin "SW1@J3") (pinfunction "SW1_SW1@J3") (pintype "bidirectional"))
      (node (ref "U1") (pin "SW1@J4") (pinfunction "SW1_SW1@J4") (pintype "bidirectional"))
      (node (ref "U1") (pin "SW1@K1") (pinfunction "SW1_SW1@K1") (pintype "bidirectional"))
      (node (ref "U1") (pin "SW1@K2") (pinfunction "SW1_SW1@K2") (pintype "bidirectional"))
      (node (ref "U1") (pin "SW1@K3") (pinfunction "SW1_SW1@K3") (pintype "bidirectional"))
      (node (ref "U1") (pin "SW1@K4") (pinfunction "SW1_SW1@K4") (pintype "bidirectional"))
      (node (ref "U1") (pin "SW1@L1") (pinfunction "SW1_SW1@L1") (pintype "bidirectional"))
      (node (ref "U1") (pin "SW1@L2") (pinfunction "SW1_SW1@L2") (pintype "bidirectional"))
      (node (ref "U1") (pin "SW1@L3") (pinfunction "SW1_SW1@L3") (pintype "bidirectional"))
      (node (ref "U1") (pin "SW1@L4") (pinfunction "SW1_SW1@L4") (pintype "bidirectional"))
      (node (ref "U1") (pin "SW1@M1") (pinfunction "SW1_SW1@M1") (pintype "bidirectional"))
      (node (ref "U1") (pin "SW1@M2") (pinfunction "SW1_SW1@M2") (pintype "bidirectional"))
      (node (ref "U1") (pin "SW1@M3") (pinfunction "SW1_SW1@M3") (pintype "bidirectional"))
      (node (ref "U1") (pin "SW1@M4") (pinfunction "SW1_SW1@M4") (pintype "bidirectional"))
    )
    (net (code "38") (name "Net-(OK1-A1)") (class "Default")
      (node (ref "OK1") (pin "1") (pinfunction "A1_1") (pintype "bidirectional"))
      (node (ref "R5") (pin "2") (pinfunction "2_2") (pintype "passive"))
    )
    (net (code "39") (name "Net-(U1-PLLFLTR)") (class "Default")
      (node (ref "R1") (pin "2") (pinfunction "2_2") (pintype "passive"))
      (node (ref "R2") (pin "1") (pinfunction "1_1") (pintype "passive"))
      (node (ref "U1") (pin "B8") (pinfunction "PLLFLTR_B8") (pintype "bidirectional"))
    )
    (net (code "40") (name "Net-(U1-V_FB)") (class "Default")
      (node (ref "R4") (pin "2") (pinfunction "2_2") (pintype "passive"))
      (node (ref "U1") (pin "B6") (pinfunction "V_FB_B6") (pintype "bidirectional"))
    )
    (net (code "41") (name "OK1E1") (class "Default")
      (node (ref "OK2") (pin "15") (pinfunction "E1_15") (pintype "bidirectional"))
      (node (ref "R23") (pin "2") (pinfunction "2_2") (pintype "passive"))
      (node (ref "U3") (pin "3") (pinfunction "INPUT1_3") (pintype "bidirectional"))
    )
    (net (code "42") (name "OK1E2") (class "Default")
      (node (ref "OK2") (pin "13") (pinfunction "E2_13") (pintype "bidirectional"))
      (node (ref "R25") (pin "2") (pinfunction "2_2") (pintype "passive"))
      (node (ref "U3") (pin "5") (pinfunction "INPUT2_5") (pintype "bidirectional"))
    )
    (net (code "43") (name "OK1E3") (class "Default")
      (node (ref "OK2") (pin "11") (pinfunction "E3_11") (pintype "bidirectional"))
      (node (ref "R27") (pin "2") (pinfunction "2_2") (pintype "passive"))
      (node (ref "U3") (pin "7") (pinfunction "INPUT3_7") (pintype "bidirectional"))
    )
    (net (code "44") (name "OK1E4") (class "Default")
      (node (ref "OK2") (pin "9") (pinfunction "E4_9") (pintype "bidirectional"))
      (node (ref "R29") (pin "2") (pinfunction "2_2") (pintype "passive"))
      (node (ref "U3") (pin "9") (pinfunction "INPUT4_9") (pintype "bidirectional"))
    )
    (net (code "45") (name "OK2E1") (class "Default")
      (node (ref "OK3") (pin "15") (pinfunction "E1_15") (pintype "bidirectional"))
      (node (ref "R24") (pin "2") (pinfunction "2_2") (pintype "passive"))
      (node (ref "U4") (pin "3") (pinfunction "INPUT1_3") (pintype "bidirectional"))
    )
    (net (code "46") (name "OK2E2") (class "Default")
      (node (ref "OK3") (pin "13") (pinfunction "E2_13") (pintype "bidirectional"))
      (node (ref "R26") (pin "2") (pinfunction "2_2") (pintype "passive"))
      (node (ref "U4") (pin "5") (pinfunction "INPUT2_5") (pintype "bidirectional"))
    )
    (net (code "47") (name "OK2E3") (class "Default")
      (node (ref "OK3") (pin "11") (pinfunction "E3_11") (pintype "bidirectional"))
      (node (ref "R28") (pin "2") (pinfunction "2_2") (pintype "passive"))
      (node (ref "U4") (pin "7") (pinfunction "INPUT3_7") (pintype "bidirectional"))
    )
    (net (code "48") (name "OK2E4") (class "Default")
      (node (ref "OK3") (pin "9") (pinfunction "E4_9") (pintype "bidirectional"))
      (node (ref "R30") (pin "2") (pinfunction "2_2") (pintype "passive"))
      (node (ref "U4") (pin "9") (pinfunction "INPUT4_9") (pintype "bidirectional"))
    )
    (net (code "49") (name "P3") (class "Default")
      (node (ref "R5") (pin "1") (pinfunction "1_1") (pintype "passive"))
      (node (ref "SJ2") (pin "2") (pinfunction "2_2") (pintype "passive"))
      (node (ref "U2") (pin "17") (pinfunction "VCC3V_17") (pintype "bidirectional"))
      (node (ref "U2") (pin "47") (pinfunction "VCC3V_47") (pintype "bidirectional"))
    )
    (net (code "50") (name "P3_SW") (class "Default")
      (node (ref "J2") (pin "4") (pinfunction "4_4") (pintype "bidirectional"))
      (node (ref "J3") (pin "2") (pinfunction "2_2") (pintype "bidirectional"))
      (node (ref "SJ2") (pin "1") (pinfunction "1_1") (pintype "passive"))
    )
    (net (code "51") (name "P18_SW1") (class "Default")
      (node (ref "OK2") (pin "1") (pinfunction "A1_1") (pintype "bidirectional"))
      (node (ref "R7") (pin "1") (pinfunction "1_1") (pintype "passive"))
    )
    (net (code "52") (name "P18_SW2") (class "Default")
      (node (ref "OK2") (pin "5") (pinfunction "A3_5") (pintype "bidirectional"))
      (node (ref "R8") (pin "1") (pinfunction "1_1") (pintype "passive"))
    )
    (net (code "53") (name "P18_SW3") (class "Default")
      (node (ref "OK3") (pin "1") (pinfunction "A1_1") (pintype "bidirectional"))
      (node (ref "R9") (pin "1") (pinfunction "1_1") (pintype "passive"))
    )
    (net (code "54") (name "P18_SW4") (class "Default")
      (node (ref "OK3") (pin "5") (pinfunction "A3_5") (pintype "bidirectional"))
      (node (ref "R10") (pin "1") (pinfunction "1_1") (pintype "passive"))
    )
    (net (code "55") (name "P18_SW5") (class "Default")
      (node (ref "OK2") (pin "3") (pinfunction "A2_3") (pintype "bidirectional"))
      (node (ref "R11") (pin "1") (pinfunction "1_1") (pintype "passive"))
    )
    (net (code "56") (name "P18_SW6") (class "Default")
      (node (ref "OK2") (pin "7") (pinfunction "A4_7") (pintype "bidirectional"))
      (node (ref "R12") (pin "1") (pinfunction "1_1") (pintype "passive"))
    )
    (net (code "57") (name "P18_SW7") (class "Default")
      (node (ref "OK3") (pin "3") (pinfunction "A2_3") (pintype "bidirectional"))
      (node (ref "R13") (pin "1") (pinfunction "1_1") (pintype "passive"))
    )
    (net (code "58") (name "P18_SW8") (class "Default")
      (node (ref "OK3") (pin "7") (pinfunction "A4_7") (pintype "bidirectional"))
      (node (ref "R14") (pin "1") (pinfunction "1_1") (pintype "passive"))
    )
    (net (code "59") (name "PBATT_SW") (class "Default")
      (node (ref "J2") (pin "5") (pinfunction "5_5") (pintype "bidirectional"))
      (node (ref "SJ1") (pin "1") (pinfunction "1_1") (pintype "passive"))
    )
    (net (code "60") (name "PGND") (class "Default")
      (node (ref "C3") (pin "2") (pinfunction "2_2") (pintype "passive"))
      (node (ref "C4") (pin "2") (pinfunction "2_2") (pintype "passive"))
      (node (ref "C5") (pin "K1") (pinfunction "K_K1") (pintype "passive"))
      (node (ref "J3") (pin "1") (pinfunction "1_1") (pintype "bidirectional"))
      (node (ref "J3") (pin "6") (pinfunction "6_6") (pintype "bidirectional"))
      (node (ref "J4") (pin "1") (pinfunction "1_1") (pintype "bidirectional"))
      (node (ref "J4") (pin "4") (pinfunction "4_4") (pintype "bidirectional"))
      (node (ref "J5") (pin "1") (pinfunction "1_1") (pintype "bidirectional"))
      (node (ref "J5") (pin "4") (pinfunction "4_4") (pintype "bidirectional"))
      (node (ref "OK1") (pin "15") (pinfunction "E1_15") (pintype "bidirectional"))
      (node (ref "R23") (pin "1") (pinfunction "1_1") (pintype "passive"))
      (node (ref "R24") (pin "1") (pinfunction "1_1") (pintype "passive"))
      (node (ref "R25") (pin "1") (pinfunction "1_1") (pintype "passive"))
      (node (ref "R26") (pin "1") (pinfunction "1_1") (pintype "passive"))
      (node (ref "R27") (pin "1") (pinfunction "1_1") (pintype "passive"))
      (node (ref "R28") (pin "1") (pinfunction "1_1") (pintype "passive"))
      (node (ref "R29") (pin "1") (pinfunction "1_1") (pintype "passive"))
      (node (ref "R3") (pin "2") (pinfunction "2_2") (pintype "passive"))
      (node (ref "R30") (pin "1") (pinfunction "1_1") (pintype "passive"))
      (node (ref "R36") (pin "2") (pinfunction "2_2") (pintype "passive"))
      (node (ref "R4") (pin "1") (pinfunction "1_1") (pintype "passive"))
      (node (ref "SJ3") (pin "1") (pinfunction "1_1") (pintype "passive"))
      (node (ref "U1") (pin "A1") (pinfunction "PGND_A1") (pintype "bidirectional"))
      (node (ref "U1") (pin "A11") (pinfunction "PGND_A11") (pintype "bidirectional"))
      (node (ref "U1") (pin "A12") (pinfunction "PGND_A12") (pintype "bidirectional"))
      (node (ref "U1") (pin "A2") (pinfunction "PGND_A2") (pintype "bidirectional"))
      (node (ref "U1") (pin "A3") (pinfunction "PGND_A3") (pintype "bidirectional"))
      (node (ref "U1") (pin "A5") (pinfunction "SENSE-_A5") (pintype "bidirectional"))
      (node (ref "U1") (pin "B1") (pinfunction "PGND_B1") (pintype "bidirectional"))
      (node (ref "U1") (pin "B10") (pinfunction "PGND_B10") (pintype "bidirectional"))
      (node (ref "U1") (pin "B11") (pinfunction "PGND_B11") (pintype "bidirectional"))
      (node (ref "U1") (pin "B12") (pinfunction "PGND_B12") (pintype "bidirectional"))
      (node (ref "U1") (pin "B2") (pinfunction "PGND_B2") (pintype "bidirectional"))
      (node (ref "U1") (pin "B3") (pinfunction "PGND_B3") (pintype "bidirectional"))
      (node (ref "U1") (pin "B4") (pinfunction "PGND_B4") (pintype "bidirectional"))
      (node (ref "U1") (pin "C1") (pinfunction "PGND_C1") (pintype "bidirectional"))
      (node (ref "U1") (pin "C10") (pinfunction "PGND_C10") (pintype "bidirectional"))
      (node (ref "U1") (pin "C11") (pinfunction "PGND_C11") (pintype "bidirectional"))
      (node (ref "U1") (pin "C12") (pinfunction "PGND_C12") (pintype "bidirectional"))
      (node (ref "U1") (pin "C2") (pinfunction "PGND_C2") (pintype "bidirectional"))
      (node (ref "U1") (pin "C3") (pinfunction "PGND_C3") (pintype "bidirectional"))
      (node (ref "U1") (pin "C4") (pinfunction "PGND_C4") (pintype "bidirectional"))
      (node (ref "U1") (pin "C5") (pinfunction "PGND_C5") (pintype "bidirectional"))
      (node (ref "U1") (pin "C6") (pinfunction "PGND_C6") (pintype "bidirectional"))
      (node (ref "U1") (pin "C7") (pinfunction "PGND_C7") (pintype "bidirectional"))
      (node (ref "U1") (pin "C8") (pinfunction "PGND_C8") (pintype "bidirectional"))
      (node (ref "U1") (pin "C9") (pinfunction "PGND_C9") (pintype "bidirectional"))
      (node (ref "U1") (pin "D1") (pinfunction "PGND_D1") (pintype "bidirectional"))
      (node (ref "U1") (pin "D10") (pinfunction "PGND_D10") (pintype "bidirectional"))
      (node (ref "U1") (pin "D11") (pinfunction "PGND_D11") (pintype "bidirectional"))
      (node (ref "U1") (pin "D12") (pinfunction "PGND_D12") (pintype "bidirectional"))
      (node (ref "U1") (pin "D2") (pinfunction "PGND_D2") (pintype "bidirectional"))
      (node (ref "U1") (pin "D3") (pinfunction "PGND_D3") (pintype "bidirectional"))
      (node (ref "U1") (pin "D4") (pinfunction "PGND_D4") (pintype "bidirectional"))
      (node (ref "U1") (pin "D5") (pinfunction "PGND_D5") (pintype "bidirectional"))
      (node (ref "U1") (pin "D6") (pinfunction "PGND_D6") (pintype "bidirectional"))
      (node (ref "U1") (pin "D7") (pinfunction "PGND_D7") (pintype "bidirectional"))
      (node (ref "U1") (pin "D8") (pinfunction "PGND_D8") (pintype "bidirectional"))
      (node (ref "U1") (pin "D9") (pinfunction "PGND_D9") (pintype "bidirectional"))
      (node (ref "U1") (pin "E10") (pinfunction "PGND_E10") (pintype "bidirectional"))
      (node (ref "U1") (pin "E11") (pinfunction "PGND_E11") (pintype "bidirectional"))
      (node (ref "U1") (pin "E12") (pinfunction "PGND_E12") (pintype "bidirectional"))
      (node (ref "U1") (pin "E3") (pinfunction "PGND_E3") (pintype "bidirectional"))
      (node (ref "U1") (pin "E4") (pinfunction "PGND_E4") (pintype "bidirectional"))
      (node (ref "U1") (pin "E5") (pinfunction "PGND_E5") (pintype "bidirectional"))
      (node (ref "U1") (pin "E6") (pinfunction "PGND_E6") (pintype "bidirectional"))
      (node (ref "U1") (pin "E7") (pinfunction "PGND_E7") (pintype "bidirectional"))
      (node (ref "U1") (pin "E8") (pinfunction "PGND_E8") (pintype "bidirectional"))
      (node (ref "U1") (pin "E9") (pinfunction "PGND_E9") (pintype "bidirectional"))
      (node (ref "U3") (pin "1") (pinfunction "GND_1") (pintype "bidirectional"))
      (node (ref "U3") (pin "10") (pinfunction "GND_10") (pintype "bidirectional"))
      (node (ref "U4") (pin "1") (pinfunction "GND_1") (pintype "bidirectional"))
      (node (ref "U4") (pin "10") (pinfunction "GND_10") (pintype "bidirectional"))
    )
    (net (code "61") (name "PGOOD_PMA") (class "Default")
      (node (ref "J3") (pin "4") (pinfunction "4_4") (pintype "bidirectional"))
      (node (ref "U1") (pin "B5") (pinfunction "PGOOD_B5") (pintype "bidirectional"))
    )
    (net (code "62") (name "RSENSE") (class "Default")
      (node (ref "R3") (pin "1") (pinfunction "1_1") (pintype "passive"))
      (node (ref "U1") (pin "A4") (pinfunction "SENSE+_A4") (pintype "bidirectional"))
      (node (ref "U1") (pin "F10") (pinfunction "R_SENSE_F10") (pintype "bidirectional"))
      (node (ref "U1") (pin "F11") (pinfunction "R_SENSE_F11") (pintype "bidirectional"))
      (node (ref "U1") (pin "F12") (pinfunction "R_SENSE_F12") (pintype "bidirectional"))
      (node (ref "U1") (pin "G10") (pinfunction "R_SENSE_G10") (pintype "bidirectional"))
      (node (ref "U1") (pin "G11") (pinfunction "R_SENSE_G11") (pintype "bidirectional"))
      (node (ref "U1") (pin "G12") (pinfunction "R_SENSE_G12") (pintype "bidirectional"))
      (node (ref "U1") (pin "G5") (pinfunction "R_SENSE_G5") (pintype "bidirectional"))
      (node (ref "U1") (pin "G6") (pinfunction "R_SENSE_G6") (pintype "bidirectional"))
      (node (ref "U1") (pin "G7") (pinfunction "R_SENSE_G7") (pintype "bidirectional"))
      (node (ref "U1") (pin "G8") (pinfunction "R_SENSE_G8") (pintype "bidirectional"))
      (node (ref "U1") (pin "G9") (pinfunction "R_SENSE_G9") (pintype "bidirectional"))
      (node (ref "U1") (pin "H10") (pinfunction "R_SENSE_H10") (pintype "bidirectional"))
      (node (ref "U1") (pin "H11") (pinfunction "R_SENSE_H11") (pintype "bidirectional"))
      (node (ref "U1") (pin "H12") (pinfunction "R_SENSE_H12") (pintype "bidirectional"))
      (node (ref "U1") (pin "H5") (pinfunction "R_SENSE_H5") (pintype "bidirectional"))
      (node (ref "U1") (pin "H6") (pinfunction "R_SENSE_H6") (pintype "bidirectional"))
      (node (ref "U1") (pin "H7") (pinfunction "R_SENSE_H7") (pintype "bidirectional"))
      (node (ref "U1") (pin "H8") (pinfunction "R_SENSE_H8") (pintype "bidirectional"))
      (node (ref "U1") (pin "H9") (pinfunction "R_SENSE_H9") (pintype "bidirectional"))
      (node (ref "U1") (pin "J5") (pinfunction "R_SENSE_J5") (pintype "bidirectional"))
      (node (ref "U1") (pin "J6") (pinfunction "R_SENSE_J6") (pintype "bidirectional"))
      (node (ref "U1") (pin "J7") (pinfunction "R_SENSE_J7") (pintype "bidirectional"))
      (node (ref "U1") (pin "K5") (pinfunction "R_SENSE_K5") (pintype "bidirectional"))
      (node (ref "U1") (pin "K6") (pinfunction "R_SENSE_K6") (pintype "bidirectional"))
      (node (ref "U1") (pin "L5") (pinfunction "R_SENSE_L5") (pintype "bidirectional"))
      (node (ref "U1") (pin "L6") (pinfunction "R_SENSE_L6") (pintype "bidirectional"))
      (node (ref "U1") (pin "M5") (pinfunction "R_SENSE_M5") (pintype "bidirectional"))
      (node (ref "U1") (pin "M6") (pinfunction "R_SENSE_M6") (pintype "bidirectional"))
    )
    (net (code "63") (name "SGND") (class "Default")
      (node (ref "R2") (pin "2") (pinfunction "2_2") (pintype "passive"))
      (node (ref "SJ3") (pin "2") (pinfunction "2_2") (pintype "passive"))
      (node (ref "SJ4") (pin "2") (pinfunction "2_2") (pintype "passive"))
      (node (ref "U1") (pin "A7") (pinfunction "SGND_A7") (pintype "bidirectional"))
    )
    (net (code "64") (name "SW_P18H1") (class "Default")
      (node (ref "R11") (pin "2") (pinfunction "2_2") (pintype "passive"))
      (node (ref "U2") (pin "35") (pinfunction "SDHC_DAT0_35") (pintype "bidirectional"))
    )
    (net (code "65") (name "SW_P18H2") (class "Default")
      (node (ref "R12") (pin "2") (pinfunction "2_2") (pintype "passive"))
      (node (ref "U2") (pin "34") (pinfunction "UART1_TX_34") (pintype "bidirectional"))
    )
    (net (code "66") (name "SW_P18H3") (class "Default")
      (node (ref "R13") (pin "2") (pinfunction "2_2") (pintype "passive"))
      (node (ref "U2") (pin "33") (pinfunction "SDHC_CMD_33") (pintype "bidirectional"))
    )
    (net (code "67") (name "SW_P18H4") (class "Default")
      (node (ref "R14") (pin "2") (pinfunction "2_2") (pintype "passive"))
      (node (ref "U2") (pin "32") (pinfunction "UART1_RX_32") (pintype "bidirectional"))
    )
    (net (code "68") (name "SW_P18L1") (class "Default")
      (node (ref "R7") (pin "2") (pinfunction "2_2") (pintype "passive"))
      (node (ref "U2") (pin "39") (pinfunction "SDHC_DAT2_39") (pintype "bidirectional"))
    )
    (net (code "69") (name "SW_P18L2") (class "Default")
      (node (ref "R8") (pin "2") (pinfunction "2_2") (pintype "passive"))
      (node (ref "U2") (pin "38") (pinfunction "UART1_CTS_38") (pintype "bidirectional"))
    )
    (net (code "70") (name "SW_P18L3") (class "Default")
      (node (ref "R9") (pin "2") (pinfunction "2_2") (pintype "passive"))
      (node (ref "U2") (pin "37") (pinfunction "SDHC_DAT1_37") (pintype "bidirectional"))
    )
    (net (code "71") (name "SW_P18L4") (class "Default")
      (node (ref "R10") (pin "2") (pinfunction "2_2") (pintype "passive"))
      (node (ref "U2") (pin "36") (pinfunction "UART1_RTS_36") (pintype "bidirectional"))
    )
    (net (code "72") (name "SW_RUNPMA") (class "Default")
      (node (ref "U1") (pin "A8") (pinfunction "RUN_A8") (pintype "bidirectional"))
      (node (ref "U2") (pin "23") (pinfunction "T2IN_23") (pintype "bidirectional"))
    )
    (net (code "73") (name "SW_TP1") (class "Default")
      (node (ref "J3") (pin "7") (pinfunction "7_7") (pintype "bidirectional"))
      (node (ref "OK1") (pin "2") (pinfunction "K1_2") (pintype "bidirectional"))
      (node (ref "U2") (pin "31") (pinfunction "SDHC_CLK_31") (pintype "bidirectional"))
    )
    (net (code "74") (name "TP1_OUT") (class "Default")
      (node (ref "J3") (pin "8") (pinfunction "8_8") (pintype "bidirectional"))
      (node (ref "J4") (pin "3") (pinfunction "3_3") (pintype "bidirectional"))
      (node (ref "J4") (pin "6") (pinfunction "6_6") (pintype "bidirectional"))
      (node (ref "J5") (pin "3") (pinfunction "3_3") (pintype "bidirectional"))
      (node (ref "J5") (pin "6") (pinfunction "6_6") (pintype "bidirectional"))
      (node (ref "OK1") (pin "16") (pinfunction "C1_16") (pintype "bidirectional"))
      (node (ref "R35") (pin "2") (pinfunction "2_2") (pintype "passive"))
      (node (ref "R36") (pin "1") (pinfunction "1_1") (pintype "passive"))
    )
    (net (code "75") (name "UART0_RX") (class "Default")
      (node (ref "J2") (pin "6") (pinfunction "6_6") (pintype "bidirectional"))
      (node (ref "J6") (pin "3") (pinfunction "3_3") (pintype "bidirectional"))
      (node (ref "U2") (pin "24") (pinfunction "UART0_RX_24") (pintype "bidirectional"))
    )
    (net (code "76") (name "UART0_TX") (class "Default")
      (node (ref "J2") (pin "3") (pinfunction "3_3") (pintype "bidirectional"))
      (node (ref "J6") (pin "2") (pinfunction "2_2") (pintype "bidirectional"))
      (node (ref "U2") (pin "26") (pinfunction "UART0_TX_26") (pintype "bidirectional"))
    )
    (net (code "77") (name "VBATT_IN") (class "Default")
      (node (ref "C1") (pin "A1") (pinfunction "A_A1") (pintype "passive"))
      (node (ref "J3") (pin "3") (pinfunction "3_3") (pintype "bidirectional"))
      (node (ref "L1") (pin "1") (pinfunction "1_1") (pintype "bidirectional"))
      (node (ref "SJ1") (pin "2") (pinfunction "2_2") (pintype "passive"))
    )
    (net (code "78") (name "VIN") (class "Default")
      (node (ref "C2") (pin "1") (pinfunction "1_1") (pintype "passive"))
      (node (ref "L1") (pin "2") (pinfunction "2_2") (pintype "bidirectional"))
      (node (ref "U1") (pin "J10") (pinfunction "V_IN_J10") (pintype "bidirectional"))
      (node (ref "U1") (pin "J11") (pinfunction "V_IN_J11") (pintype "bidirectional"))
      (node (ref "U1") (pin "J12") (pinfunction "V_IN_J12") (pintype "bidirectional"))
      (node (ref "U1") (pin "K10") (pinfunction "V_IN_K10") (pintype "bidirectional"))
      (node (ref "U1") (pin "K11") (pinfunction "V_IN_K11") (pintype "bidirectional"))
      (node (ref "U1") (pin "K12") (pinfunction "V_IN_K12") (pintype "bidirectional"))
      (node (ref "U1") (pin "L10") (pinfunction "V_IN_L10") (pintype "bidirectional"))
      (node (ref "U1") (pin "L11") (pinfunction "V_IN_L11") (pintype "bidirectional"))
      (node (ref "U1") (pin "L12") (pinfunction "V_IN_L12") (pintype "bidirectional"))
      (node (ref "U1") (pin "M10") (pinfunction "V_IN_M10") (pintype "bidirectional"))
      (node (ref "U1") (pin "M11") (pinfunction "V_IN_M11") (pintype "bidirectional"))
      (node (ref "U1") (pin "M12") (pinfunction "V_IN_M12") (pintype "bidirectional"))
    )
    (net (code "79") (name "VOUT") (class "Default")
      (node (ref "C3") (pin "1") (pinfunction "1_1") (pintype "passive"))
      (node (ref "C4") (pin "1") (pinfunction "1_1") (pintype "passive"))
      (node (ref "L3") (pin "1") (pinfunction "1_1") (pintype "bidirectional"))
      (node (ref "U1") (pin "E1") (pinfunction "V_OUT_E1") (pintype "bidirectional"))
      (node (ref "U1") (pin "E2") (pinfunction "V_OUT_E2") (pintype "bidirectional"))
      (node (ref "U1") (pin "F1") (pinfunction "V_OUT_F1") (pintype "bidirectional"))
      (node (ref "U1") (pin "F2") (pinfunction "V_OUT_F2") (pintype "bidirectional"))
      (node (ref "U1") (pin "F3") (pinfunction "V_OUT_F3") (pintype "bidirectional"))
      (node (ref "U1") (pin "F4") (pinfunction "V_OUT_F4") (pintype "bidirectional"))
      (node (ref "U1") (pin "G1") (pinfunction "V_OUT_G1") (pintype "bidirectional"))
      (node (ref "U1") (pin "G2") (pinfunction "V_OUT_G2") (pintype "bidirectional"))
      (node (ref "U1") (pin "G3") (pinfunction "V_OUT_G3") (pintype "bidirectional"))
      (node (ref "U1") (pin "G4") (pinfunction "V_OUT_G4") (pintype "bidirectional"))
      (node (ref "U1") (pin "H2") (pinfunction "V_OUT_H2") (pintype "bidirectional"))
      (node (ref "U1") (pin "H3") (pinfunction "V_OUT_H3") (pintype "bidirectional"))
      (node (ref "U1") (pin "H4") (pinfunction "V_OUT_H4") (pintype "bidirectional"))
      (node (ref "U1") (pin "VOUT") (pinfunction "V_OUT_VOUT") (pintype "bidirectional"))
    )
    (net (code "80") (name "VOUTA") (class "Default")
      (node (ref "C5") (pin "A1") (pinfunction "A_A1") (pintype "passive"))
      (node (ref "J3") (pin "5") (pinfunction "5_5") (pintype "bidirectional"))
      (node (ref "L3") (pin "2") (pinfunction "2_2") (pintype "bidirectional"))
      (node (ref "Q1") (pin "D") (pinfunction "D_D") (pintype "bidirectional"))
      (node (ref "Q3") (pin "D") (pinfunction "D_D") (pintype "bidirectional"))
      (node (ref "Q5") (pin "D") (pinfunction "D_D") (pintype "bidirectional"))
      (node (ref "Q7") (pin "D") (pinfunction "D_D") (pintype "bidirectional"))
      (node (ref "R15") (pin "1") (pinfunction "1_1") (pintype "passive"))
      (node (ref "R16") (pin "1") (pinfunction "1_1") (pintype "passive"))
      (node (ref "R17") (pin "1") (pinfunction "1_1") (pintype "passive"))
      (node (ref "R18") (pin "1") (pinfunction "1_1") (pintype "passive"))
      (node (ref "R19") (pin "1") (pinfunction "1_1") (pintype "passive"))
      (node (ref "R20") (pin "1") (pinfunction "1_1") (pintype "passive"))
      (node (ref "R21") (pin "1") (pinfunction "1_1") (pintype "passive"))
      (node (ref "R22") (pin "1") (pinfunction "1_1") (pintype "passive"))
      (node (ref "R31") (pin "2") (pinfunction "2_2") (pintype "passive"))
      (node (ref "R32") (pin "2") (pinfunction "2_2") (pintype "passive"))
      (node (ref "R33") (pin "2") (pinfunction "2_2") (pintype "passive"))
      (node (ref "R34") (pin "2") (pinfunction "2_2") (pintype "passive"))
      (node (ref "R35") (pin "1") (pinfunction "1_1") (pintype "passive"))
      (node (ref "U3") (pin "11") (pinfunction "V+_11") (pintype "bidirectional"))
      (node (ref "U3") (pin "13") (pinfunction "SENSE4_13") (pintype "bidirectional"))
      (node (ref "U3") (pin "15") (pinfunction "SENSE3_15") (pintype "bidirectional"))
      (node (ref "U3") (pin "17") (pinfunction "SENSE2_17") (pintype "bidirectional"))
      (node (ref "U3") (pin "19") (pinfunction "SENSE1_19") (pintype "bidirectional"))
      (node (ref "U3") (pin "20") (pinfunction "V+_20") (pintype "bidirectional"))
      (node (ref "U4") (pin "11") (pinfunction "V+_11") (pintype "bidirectional"))
      (node (ref "U4") (pin "13") (pinfunction "SENSE4_13") (pintype "bidirectional"))
      (node (ref "U4") (pin "15") (pinfunction "SENSE3_15") (pintype "bidirectional"))
      (node (ref "U4") (pin "17") (pinfunction "SENSE2_17") (pintype "bidirectional"))
      (node (ref "U4") (pin "19") (pinfunction "SENSE1_19") (pintype "bidirectional"))
      (node (ref "U4") (pin "20") (pinfunction "V+_20") (pintype "bidirectional"))
    )
    (net (code "81") (name "unconnected-(J1-+5V_SW-Pad33)") (class "Default")
      (node (ref "J1") (pin "33") (pinfunction "+5V_SW_33") (pintype "bidirectional"))
    )
    (net (code "82") (name "unconnected-(J1-+5V_SYS-Pad77)") (class "Default")
      (node (ref "J1") (pin "77") (pinfunction "+5V_SYS_77") (pintype "bidirectional"))
    )
    (net (code "83") (name "unconnected-(J1-+5V_SYS-Pad78)") (class "Default")
      (node (ref "J1") (pin "78") (pinfunction "+5V_SYS_78") (pintype "bidirectional"))
    )
    (net (code "84") (name "unconnected-(J1-+5V_USB-Pad32)") (class "Default")
      (node (ref "J1") (pin "32") (pinfunction "+5V_USB_32") (pintype "bidirectional"))
    )
    (net (code "85") (name "unconnected-(J1--CTS_MHX-Pad35)") (class "Default")
      (node (ref "J1") (pin "35") (pinfunction "-CTS_MHX_35") (pintype "bidirectional"))
    )
    (net (code "86") (name "unconnected-(J1--DSR_MHX-Pad37)") (class "Default")
      (node (ref "J1") (pin "37") (pinfunction "-DSR_MHX_37") (pintype "bidirectional"))
    )
    (net (code "87") (name "unconnected-(J1--DTR_MHX-Pad38)") (class "Default")
      (node (ref "J1") (pin "38") (pinfunction "-DTR_MHX_38") (pintype "bidirectional"))
    )
    (net (code "88") (name "unconnected-(J1--FAULT-Pad25)") (class "Default")
      (node (ref "J1") (pin "25") (pinfunction "-FAULT_25") (pintype "bidirectional"))
    )
    (net (code "89") (name "unconnected-(J1--RESET-Pad29)") (class "Default")
      (node (ref "J1") (pin "29") (pinfunction "-RESET_29") (pintype "bidirectional"))
    )
    (net (code "90") (name "unconnected-(J1--RST_MHX-Pad34)") (class "Default")
      (node (ref "J1") (pin "34") (pinfunction "-RST_MHX_34") (pintype "bidirectional"))
    )
    (net (code "91") (name "unconnected-(J1--RTS_MHX-Pad36)") (class "Default")
      (node (ref "J1") (pin "36") (pinfunction "-RTS_MHX_36") (pintype "bidirectional"))
    )
    (net (code "92") (name "unconnected-(J1-OFF_VCC-Pad31)") (class "Default")
      (node (ref "J1") (pin "31") (pinfunction "OFF_VCC_31") (pintype "bidirectional"))
    )
    (net (code "93") (name "unconnected-(J1-P1.0-Pad68)") (class "Default")
      (node (ref "J1") (pin "68") (pinfunction "P1.0_68") (pintype "bidirectional"))
    )
    (net (code "94") (name "unconnected-(J1-P1.1-Pad67)") (class "Default")
      (node (ref "J1") (pin "67") (pinfunction "P1.1_67") (pintype "bidirectional"))
    )
    (net (code "95") (name "unconnected-(J1-P1.2-Pad66)") (class "Default")
      (node (ref "J1") (pin "66") (pinfunction "P1.2_66") (pintype "bidirectional"))
    )
    (net (code "96") (name "unconnected-(J1-P1.3-Pad65)") (class "Default")
      (node (ref "J1") (pin "65") (pinfunction "P1.3_65") (pintype "bidirectional"))
    )
    (net (code "97") (name "unconnected-(J1-P1.4-Pad64)") (class "Default")
      (node (ref "J1") (pin "64") (pinfunction "P1.4_64") (pintype "bidirectional"))
    )
    (net (code "98") (name "unconnected-(J1-P1.5-Pad63)") (class "Default")
      (node (ref "J1") (pin "63") (pinfunction "P1.5_63") (pintype "bidirectional"))
    )
    (net (code "99") (name "unconnected-(J1-P1.6-Pad62)") (class "Default")
      (node (ref "J1") (pin "62") (pinfunction "P1.6_62") (pintype "bidirectional"))
    )
    (net (code "100") (name "unconnected-(J1-P1.7-Pad61)") (class "Default")
      (node (ref "J1") (pin "61") (pinfunction "P1.7_61") (pintype "bidirectional"))
    )
    (net (code "101") (name "unconnected-(J1-P2.0-Pad76)") (class "Default")
      (node (ref "J1") (pin "76") (pinfunction "P2.0_76") (pintype "bidirectional"))
    )
    (net (code "102") (name "unconnected-(J1-P2.1-Pad75)") (class "Default")
      (node (ref "J1") (pin "75") (pinfunction "P2.1_75") (pintype "bidirectional"))
    )
    (net (code "103") (name "unconnected-(J1-P2.2-Pad74)") (class "Default")
      (node (ref "J1") (pin "74") (pinfunction "P2.2_74") (pintype "bidirectional"))
    )
    (net (code "104") (name "unconnected-(J1-P2.3-Pad73)") (class "Default")
      (node (ref "J1") (pin "73") (pinfunction "P2.3_73") (pintype "bidirectional"))
    )
    (net (code "105") (name "unconnected-(J1-P2.4-Pad72)") (class "Default")
      (node (ref "J1") (pin "72") (pinfunction "P2.4_72") (pintype "bidirectional"))
    )
    (net (code "106") (name "unconnected-(J1-P2.5-Pad71)") (class "Default")
      (node (ref "J1") (pin "71") (pinfunction "P2.5_71") (pintype "bidirectional"))
    )
    (net (code "107") (name "unconnected-(J1-P2.6-Pad70)") (class "Default")
      (node (ref "J1") (pin "70") (pinfunction "P2.6_70") (pintype "bidirectional"))
    )
    (net (code "108") (name "unconnected-(J1-P2.7-Pad69)") (class "Default")
      (node (ref "J1") (pin "69") (pinfunction "P2.7_69") (pintype "bidirectional"))
    )
    (net (code "109") (name "unconnected-(J1-P3.0-Pad24)") (class "Default")
      (node (ref "J1") (pin "24") (pinfunction "P3.0_24") (pintype "bidirectional"))
    )
    (net (code "110") (name "unconnected-(J1-P3.1-Pad23)") (class "Default")
      (node (ref "J1") (pin "23") (pinfunction "P3.1_23") (pintype "bidirectional"))
    )
    (net (code "111") (name "unconnected-(J1-P3.2-Pad22)") (class "Default")
      (node (ref "J1") (pin "22") (pinfunction "P3.2_22") (pintype "bidirectional"))
    )
    (net (code "112") (name "unconnected-(J1-P3.3-Pad21)") (class "Default")
      (node (ref "J1") (pin "21") (pinfunction "P3.3_21") (pintype "bidirectional"))
    )
    (net (code "113") (name "unconnected-(J1-P3.4-Pad20)") (class "Default")
      (node (ref "J1") (pin "20") (pinfunction "P3.4_20") (pintype "bidirectional"))
    )
    (net (code "114") (name "unconnected-(J1-P3.5-Pad19)") (class "Default")
      (node (ref "J1") (pin "19") (pinfunction "P3.5_19") (pintype "bidirectional"))
    )
    (net (code "115") (name "unconnected-(J1-P3.6-Pad18)") (class "Default")
      (node (ref "J1") (pin "18") (pinfunction "P3.6_18") (pintype "bidirectional"))
    )
    (net (code "116") (name "unconnected-(J1-P3.7-Pad17)") (class "Default")
      (node (ref "J1") (pin "17") (pinfunction "P3.7_17") (pintype "bidirectional"))
    )
    (net (code "117") (name "unconnected-(J1-P4.0-Pad16)") (class "Default")
      (node (ref "J1") (pin "16") (pinfunction "P4.0_16") (pintype "bidirectional"))
    )
    (net (code "118") (name "unconnected-(J1-P4.1-Pad15)") (class "Default")
      (node (ref "J1") (pin "15") (pinfunction "P4.1_15") (pintype "bidirectional"))
    )
    (net (code "119") (name "unconnected-(J1-P4.2-Pad14)") (class "Default")
      (node (ref "J1") (pin "14") (pinfunction "P4.2_14") (pintype "bidirectional"))
    )
    (net (code "120") (name "unconnected-(J1-P4.3-Pad13)") (class "Default")
      (node (ref "J1") (pin "13") (pinfunction "P4.3_13") (pintype "bidirectional"))
    )
    (net (code "121") (name "unconnected-(J1-P4.4-Pad12)") (class "Default")
      (node (ref "J1") (pin "12") (pinfunction "P4.4_12") (pintype "bidirectional"))
    )
    (net (code "122") (name "unconnected-(J1-P4.5-Pad11)") (class "Default")
      (node (ref "J1") (pin "11") (pinfunction "P4.5_11") (pintype "bidirectional"))
    )
    (net (code "123") (name "unconnected-(J1-P4.6-Pad10)") (class "Default")
      (node (ref "J1") (pin "10") (pinfunction "P4.6_10") (pintype "bidirectional"))
    )
    (net (code "124") (name "unconnected-(J1-P4.7-Pad9)") (class "Default")
      (node (ref "J1") (pin "9") (pinfunction "P4.7_9") (pintype "bidirectional"))
    )
    (net (code "125") (name "unconnected-(J1-P5.0-Pad8)") (class "Default")
      (node (ref "J1") (pin "8") (pinfunction "P5.0_8") (pintype "bidirectional"))
    )
    (net (code "126") (name "unconnected-(J1-P5.1-Pad7)") (class "Default")
      (node (ref "J1") (pin "7") (pinfunction "P5.1_7") (pintype "bidirectional"))
    )
    (net (code "127") (name "unconnected-(J1-P5.2-Pad6)") (class "Default")
      (node (ref "J1") (pin "6") (pinfunction "P5.2_6") (pintype "bidirectional"))
    )
    (net (code "128") (name "unconnected-(J1-P5.3-Pad5)") (class "Default")
      (node (ref "J1") (pin "5") (pinfunction "P5.3_5") (pintype "bidirectional"))
    )
    (net (code "129") (name "unconnected-(J1-P5.4-Pad4)") (class "Default")
      (node (ref "J1") (pin "4") (pinfunction "P5.4_4") (pintype "bidirectional"))
    )
    (net (code "130") (name "unconnected-(J1-P5.5-Pad3)") (class "Default")
      (node (ref "J1") (pin "3") (pinfunction "P5.5_3") (pintype "bidirectional"))
    )
    (net (code "131") (name "unconnected-(J1-P5.6-Pad2)") (class "Default")
      (node (ref "J1") (pin "2") (pinfunction "P5.6_2") (pintype "bidirectional"))
    )
    (net (code "132") (name "unconnected-(J1-P5.7-Pad1)") (class "Default")
      (node (ref "J1") (pin "1") (pinfunction "P5.7_1") (pintype "bidirectional"))
    )
    (net (code "133") (name "unconnected-(J1-P6.0-Pad60)") (class "Default")
      (node (ref "J1") (pin "60") (pinfunction "P6.0_60") (pintype "bidirectional"))
    )
    (net (code "134") (name "unconnected-(J1-P6.1-Pad59)") (class "Default")
      (node (ref "J1") (pin "59") (pinfunction "P6.1_59") (pintype "bidirectional"))
    )
    (net (code "135") (name "unconnected-(J1-P6.2-Pad58)") (class "Default")
      (node (ref "J1") (pin "58") (pinfunction "P6.2_58") (pintype "bidirectional"))
    )
    (net (code "136") (name "unconnected-(J1-P6.3-Pad57)") (class "Default")
      (node (ref "J1") (pin "57") (pinfunction "P6.3_57") (pintype "bidirectional"))
    )
    (net (code "137") (name "unconnected-(J1-P6.4-Pad56)") (class "Default")
      (node (ref "J1") (pin "56") (pinfunction "P6.4_56") (pintype "bidirectional"))
    )
    (net (code "138") (name "unconnected-(J1-P6.5-Pad55)") (class "Default")
      (node (ref "J1") (pin "55") (pinfunction "P6.5_55") (pintype "bidirectional"))
    )
    (net (code "139") (name "unconnected-(J1-P6.6-Pad54)") (class "Default")
      (node (ref "J1") (pin "54") (pinfunction "P6.6_54") (pintype "bidirectional"))
    )
    (net (code "140") (name "unconnected-(J1-P6.7-Pad53)") (class "Default")
      (node (ref "J1") (pin "53") (pinfunction "P6.7_53") (pintype "bidirectional"))
    )
    (net (code "141") (name "unconnected-(J1-RSVD0-Pad44)") (class "Default")
      (node (ref "J1") (pin "44") (pinfunction "RSVD0_44") (pintype "bidirectional"))
    )
    (net (code "142") (name "unconnected-(J1-RSVD1-Pad45)") (class "Default")
      (node (ref "J1") (pin "45") (pinfunction "RSVD1_45") (pintype "bidirectional"))
    )
    (net (code "143") (name "unconnected-(J1-RSVD2-Pad46)") (class "Default")
      (node (ref "J1") (pin "46") (pinfunction "RSVD2_46") (pintype "bidirectional"))
    )
    (net (code "144") (name "unconnected-(J1-RXD_MHX-Pad40)") (class "Default")
      (node (ref "J1") (pin "40") (pinfunction "RXD_MHX_40") (pintype "bidirectional"))
    )
    (net (code "145") (name "unconnected-(J1-SENSE-Pad27)") (class "Default")
      (node (ref "J1") (pin "27") (pinfunction "SENSE_27") (pintype "bidirectional"))
    )
    (net (code "146") (name "unconnected-(J1-SW0-Pad85)") (class "Default")
      (node (ref "J1") (pin "85") (pinfunction "SW0_85") (pintype "bidirectional"))
    )
    (net (code "147") (name "unconnected-(J1-SW0-Pad86)") (class "Default")
      (node (ref "J1") (pin "86") (pinfunction "SW0_86") (pintype "bidirectional"))
    )
    (net (code "148") (name "unconnected-(J1-SW1-Pad87)") (class "Default")
      (node (ref "J1") (pin "87") (pinfunction "SW1_87") (pintype "bidirectional"))
    )
    (net (code "149") (name "unconnected-(J1-SW1-Pad88)") (class "Default")
      (node (ref "J1") (pin "88") (pinfunction "SW1_88") (pintype "bidirectional"))
    )
    (net (code "150") (name "unconnected-(J1-SW2-Pad89)") (class "Default")
      (node (ref "J1") (pin "89") (pinfunction "SW2_89") (pintype "bidirectional"))
    )
    (net (code "151") (name "unconnected-(J1-SW2-Pad90)") (class "Default")
      (node (ref "J1") (pin "90") (pinfunction "SW2_90") (pintype "bidirectional"))
    )
    (net (code "152") (name "unconnected-(J1-SW3-Pad91)") (class "Default")
      (node (ref "J1") (pin "91") (pinfunction "SW3_91") (pintype "bidirectional"))
    )
    (net (code "153") (name "unconnected-(J1-SW3-Pad92)") (class "Default")
      (node (ref "J1") (pin "92") (pinfunction "SW3_92") (pintype "bidirectional"))
    )
    (net (code "154") (name "unconnected-(J1-SW4-Pad93)") (class "Default")
      (node (ref "J1") (pin "93") (pinfunction "SW4_93") (pintype "bidirectional"))
    )
    (net (code "155") (name "unconnected-(J1-SW4-Pad94)") (class "Default")
      (node (ref "J1") (pin "94") (pinfunction "SW4_94") (pintype "bidirectional"))
    )
    (net (code "156") (name "unconnected-(J1-SW5-Pad95)") (class "Default")
      (node (ref "J1") (pin "95") (pinfunction "SW5_95") (pintype "bidirectional"))
    )
    (net (code "157") (name "unconnected-(J1-SW5-Pad96)") (class "Default")
      (node (ref "J1") (pin "96") (pinfunction "SW5_96") (pintype "bidirectional"))
    )
    (net (code "158") (name "unconnected-(J1-TXD_MHX-Pad39)") (class "Default")
      (node (ref "J1") (pin "39") (pinfunction "TXD_MHX_39") (pintype "bidirectional"))
    )
    (net (code "159") (name "unconnected-(J1-USER0-Pad47)") (class "Default")
      (node (ref "J1") (pin "47") (pinfunction "USER0_47") (pintype "bidirectional"))
    )
    (net (code "160") (name "unconnected-(J1-USER1-Pad48)") (class "Default")
      (node (ref "J1") (pin "48") (pinfunction "USER1_48") (pintype "bidirectional"))
    )
    (net (code "161") (name "unconnected-(J1-USER2-Pad49)") (class "Default")
      (node (ref "J1") (pin "49") (pinfunction "USER2_49") (pintype "bidirectional"))
    )
    (net (code "162") (name "unconnected-(J1-USER3-Pad50)") (class "Default")
      (node (ref "J1") (pin "50") (pinfunction "USER3_50") (pintype "bidirectional"))
    )
    (net (code "163") (name "unconnected-(J1-USER4-Pad51)") (class "Default")
      (node (ref "J1") (pin "51") (pinfunction "USER4_51") (pintype "bidirectional"))
    )
    (net (code "164") (name "unconnected-(J1-USER5-Pad52)") (class "Default")
      (node (ref "J1") (pin "52") (pinfunction "USER5_52") (pintype "bidirectional"))
    )
    (net (code "165") (name "unconnected-(J1-USER6-Pad99)") (class "Default")
      (node (ref "J1") (pin "99") (pinfunction "USER6_99") (pintype "bidirectional"))
    )
    (net (code "166") (name "unconnected-(J1-USER7-Pad100)") (class "Default")
      (node (ref "J1") (pin "100") (pinfunction "USER7_100") (pintype "bidirectional"))
    )
    (net (code "167") (name "unconnected-(J1-USER8-Pad101)") (class "Default")
      (node (ref "J1") (pin "101") (pinfunction "USER8_101") (pintype "bidirectional"))
    )
    (net (code "168") (name "unconnected-(J1-USER9-Pad102)") (class "Default")
      (node (ref "J1") (pin "102") (pinfunction "USER9_102") (pintype "bidirectional"))
    )
    (net (code "169") (name "unconnected-(J1-USER10-Pad103)") (class "Default")
      (node (ref "J1") (pin "103") (pinfunction "USER10_103") (pintype "bidirectional"))
    )
    (net (code "170") (name "unconnected-(J1-USER11-Pad104)") (class "Default")
      (node (ref "J1") (pin "104") (pinfunction "USER11_104") (pintype "bidirectional"))
    )
    (net (code "171") (name "unconnected-(J1-VBACKUP-Pad42)") (class "Default")
      (node (ref "J1") (pin "42") (pinfunction "VBACKUP_42") (pintype "bidirectional"))
    )
    (net (code "172") (name "unconnected-(J1-VBATT-Pad97)") (class "Default")
      (node (ref "J1") (pin "97") (pinfunction "VBATT_97") (pintype "bidirectional"))
    )
    (net (code "173") (name "unconnected-(J1-VBATT-Pad98)") (class "Default")
      (node (ref "J1") (pin "98") (pinfunction "VBATT_98") (pintype "bidirectional"))
    )
    (net (code "174") (name "unconnected-(J1-VCC_SYS-Pad79)") (class "Default")
      (node (ref "J1") (pin "79") (pinfunction "VCC_SYS_79") (pintype "bidirectional"))
    )
    (net (code "175") (name "unconnected-(J1-VCC_SYS-Pad80)") (class "Default")
      (node (ref "J1") (pin "80") (pinfunction "VCC_SYS_80") (pintype "bidirectional"))
    )
    (net (code "176") (name "unconnected-(J1-VEREF+-Pad28)") (class "Default")
      (node (ref "J1") (pin "28") (pinfunction "VEREF+_28") (pintype "bidirectional"))
    )
    (net (code "177") (name "unconnected-(J1-VREF+-Pad26)") (class "Default")
      (node (ref "J1") (pin "26") (pinfunction "VREF+_26") (pintype "bidirectional"))
    )
    (net (code "178") (name "unconnected-(J1-VREF--Pad30)") (class "Default")
      (node (ref "J1") (pin "30") (pinfunction "VREF-_30") (pintype "bidirectional"))
    )
    (net (code "179") (name "unconnected-(J4-Pad2)") (class "Default")
      (node (ref "J4") (pin "2") (pinfunction "2_2") (pintype "bidirectional"))
    )
    (net (code "180") (name "unconnected-(J4-Pad5)") (class "Default")
      (node (ref "J4") (pin "5") (pinfunction "5_5") (pintype "bidirectional"))
    )
    (net (code "181") (name "unconnected-(J4-Pad9)") (class "Default")
      (node (ref "J4") (pin "9") (pinfunction "9_9") (pintype "bidirectional"))
    )
    (net (code "182") (name "unconnected-(J4-Pad12)") (class "Default")
      (node (ref "J4") (pin "12") (pinfunction "12_12") (pintype "bidirectional"))
    )
    (net (code "183") (name "unconnected-(J5-Pad2)") (class "Default")
      (node (ref "J5") (pin "2") (pinfunction "2_2") (pintype "bidirectional"))
    )
    (net (code "184") (name "unconnected-(J5-Pad5)") (class "Default")
      (node (ref "J5") (pin "5") (pinfunction "5_5") (pintype "bidirectional"))
    )
    (net (code "185") (name "unconnected-(J5-Pad9)") (class "Default")
      (node (ref "J5") (pin "9") (pinfunction "9_9") (pintype "bidirectional"))
    )
    (net (code "186") (name "unconnected-(J5-Pad12)") (class "Default")
      (node (ref "J5") (pin "12") (pinfunction "12_12") (pintype "bidirectional"))
    )
    (net (code "187") (name "unconnected-(OK1-A2-Pad3)") (class "Default")
      (node (ref "OK1") (pin "3") (pinfunction "A2_3") (pintype "bidirectional"))
    )
    (net (code "188") (name "unconnected-(OK1-A3-Pad5)") (class "Default")
      (node (ref "OK1") (pin "5") (pinfunction "A3_5") (pintype "bidirectional"))
    )
    (net (code "189") (name "unconnected-(OK1-A4-Pad7)") (class "Default")
      (node (ref "OK1") (pin "7") (pinfunction "A4_7") (pintype "bidirectional"))
    )
    (net (code "190") (name "unconnected-(OK1-C2-Pad14)") (class "Default")
      (node (ref "OK1") (pin "14") (pinfunction "C2_14") (pintype "bidirectional"))
    )
    (net (code "191") (name "unconnected-(OK1-C3-Pad12)") (class "Default")
      (node (ref "OK1") (pin "12") (pinfunction "C3_12") (pintype "bidirectional"))
    )
    (net (code "192") (name "unconnected-(OK1-C4-Pad10)") (class "Default")
      (node (ref "OK1") (pin "10") (pinfunction "C4_10") (pintype "bidirectional"))
    )
    (net (code "193") (name "unconnected-(OK1-E2-Pad13)") (class "Default")
      (node (ref "OK1") (pin "13") (pinfunction "E2_13") (pintype "bidirectional"))
    )
    (net (code "194") (name "unconnected-(OK1-E3-Pad11)") (class "Default")
      (node (ref "OK1") (pin "11") (pinfunction "E3_11") (pintype "bidirectional"))
    )
    (net (code "195") (name "unconnected-(OK1-E4-Pad9)") (class "Default")
      (node (ref "OK1") (pin "9") (pinfunction "E4_9") (pintype "bidirectional"))
    )
    (net (code "196") (name "unconnected-(OK1-K2-Pad4)") (class "Default")
      (node (ref "OK1") (pin "4") (pinfunction "K2_4") (pintype "bidirectional"))
    )
    (net (code "197") (name "unconnected-(OK1-K3-Pad6)") (class "Default")
      (node (ref "OK1") (pin "6") (pinfunction "K3_6") (pintype "bidirectional"))
    )
    (net (code "198") (name "unconnected-(OK1-K4-Pad8)") (class "Default")
      (node (ref "OK1") (pin "8") (pinfunction "K4_8") (pintype "bidirectional"))
    )
    (net (code "199") (name "unconnected-(U1-COMP-PadB7)") (class "Default")
      (node (ref "U1") (pin "B7") (pinfunction "COMP_B7") (pintype "bidirectional"))
    )
    (net (code "200") (name "unconnected-(U1-EXTV_CC-PadF6)") (class "Default")
      (node (ref "U1") (pin "F6") (pinfunction "EXTV_CC_F6") (pintype "bidirectional"))
    )
    (net (code "201") (name "unconnected-(U1-PLLIN-PadB9)") (class "Default")
      (node (ref "U1") (pin "B9") (pinfunction "PLLIN_B9") (pintype "bidirectional"))
    )
    (net (code "202") (name "unconnected-(U1-SS-PadA6)") (class "Default")
      (node (ref "U1") (pin "A6") (pinfunction "SS_A6") (pintype "bidirectional"))
    )
    (net (code "203") (name "unconnected-(U1-STBYMD-PadA10)") (class "Default")
      (node (ref "U1") (pin "A10") (pinfunction "STBYMD_A10") (pintype "bidirectional"))
    )
    (net (code "204") (name "unconnected-(U2-ADC_IN0-Pad2)") (class "Default")
      (node (ref "U2") (pin "2") (pinfunction "ADC_IN0_2") (pintype "bidirectional"))
    )
    (net (code "205") (name "unconnected-(U2-ADC_IN1-Pad1)") (class "Default")
      (node (ref "U2") (pin "1") (pinfunction "ADC_IN1_1") (pintype "bidirectional"))
    )
    (net (code "206") (name "unconnected-(U2-ADC_IN2-Pad4)") (class "Default")
      (node (ref "U2") (pin "4") (pinfunction "ADC_IN2_4") (pintype "bidirectional"))
    )
    (net (code "207") (name "unconnected-(U2-ADC_IN3-Pad3)") (class "Default")
      (node (ref "U2") (pin "3") (pinfunction "ADC_IN3_3") (pintype "bidirectional"))
    )
    (net (code "208") (name "unconnected-(U2-ADC_IN4-Pad6)") (class "Default")
      (node (ref "U2") (pin "6") (pinfunction "ADC_IN4_6") (pintype "bidirectional"))
    )
    (net (code "209") (name "unconnected-(U2-ADC_IN7-Pad5)") (class "Default")
      (node (ref "U2") (pin "5") (pinfunction "ADC_IN7_5") (pintype "bidirectional"))
    )
    (net (code "210") (name "unconnected-(U2-AGND-Pad8)") (class "Default")
      (node (ref "U2") (pin "8") (pinfunction "AGND_8") (pintype "bidirectional"))
    )
    (net (code "211") (name "unconnected-(U2-CAN1_RX-Pad20)") (class "Default")
      (node (ref "U2") (pin "20") (pinfunction "CAN1_RX_20") (pintype "bidirectional"))
    )
    (net (code "212") (name "unconnected-(U2-CAN1_TX-Pad22)") (class "Default")
      (node (ref "U2") (pin "22") (pinfunction "CAN1_TX_22") (pintype "bidirectional"))
    )
    (net (code "213") (name "unconnected-(U2-ERX_JM-Pad44)") (class "Default")
      (node (ref "U2") (pin "44") (pinfunction "ERX_JM_44") (pintype "bidirectional"))
    )
    (net (code "214") (name "unconnected-(U2-ERX_JP-Pad43)") (class "Default")
      (node (ref "U2") (pin "43") (pinfunction "ERX_JP_43") (pintype "bidirectional"))
    )
    (net (code "215") (name "unconnected-(U2-ETX_JM-Pad46)") (class "Default")
      (node (ref "U2") (pin "46") (pinfunction "ETX_JM_46") (pintype "bidirectional"))
    )
    (net (code "216") (name "unconnected-(U2-ETX_JP-Pad45)") (class "Default")
      (node (ref "U2") (pin "45") (pinfunction "ETX_JP_45") (pintype "bidirectional"))
    )
    (net (code "217") (name "unconnected-(U2-IRQ2-Pad50)") (class "Default")
      (node (ref "U2") (pin "50") (pinfunction "IRQ2_50") (pintype "bidirectional"))
    )
    (net (code "218") (name "unconnected-(U2-IRQ3-Pad49)") (class "Default")
      (node (ref "U2") (pin "49") (pinfunction "IRQ3_49") (pintype "bidirectional"))
    )
    (net (code "219") (name "unconnected-(U2-IRQ7-Pad9)") (class "Default")
      (node (ref "U2") (pin "9") (pinfunction "IRQ7_9") (pintype "bidirectional"))
    )
    (net (code "220") (name "unconnected-(U2-LINKLED-Pad42)") (class "Default")
      (node (ref "U2") (pin "42") (pinfunction "LINKLED_42") (pintype "bidirectional"))
    )
    (net (code "221") (name "unconnected-(U2-OW_DAT-Pad12)") (class "Default")
      (node (ref "U2") (pin "12") (pinfunction "OW_DAT_12") (pintype "bidirectional"))
    )
    (net (code "222") (name "unconnected-(U2-RSTI-Pad11)") (class "Default")
      (node (ref "U2") (pin "11") (pinfunction "RSTI_11") (pintype "bidirectional"))
    )
    (net (code "223") (name "unconnected-(U2-SDHC_DAT3-Pad15)") (class "Default")
      (node (ref "U2") (pin "15") (pinfunction "SDHC_DAT3_15") (pintype "bidirectional"))
    )
    (net (code "224") (name "unconnected-(U2-SPEEDLED-Pad40)") (class "Default")
      (node (ref "U2") (pin "40") (pinfunction "SPEEDLED_40") (pintype "bidirectional"))
    )
    (net (code "225") (name "unconnected-(U2-T0IN-Pad19)") (class "Default")
      (node (ref "U2") (pin "19") (pinfunction "T0IN_19") (pintype "bidirectional"))
    )
    (net (code "226") (name "unconnected-(U2-T1IN-Pad21)") (class "Default")
      (node (ref "U2") (pin "21") (pinfunction "T1IN_21") (pintype "bidirectional"))
    )
    (net (code "227") (name "unconnected-(U2-T3IN-Pad25)") (class "Default")
      (node (ref "U2") (pin "25") (pinfunction "T3IN_25") (pintype "bidirectional"))
    )
    (net (code "228") (name "unconnected-(U2-UART0_CTS-Pad30)") (class "Default")
      (node (ref "U2") (pin "30") (pinfunction "UART0_CTS_30") (pintype "bidirectional"))
    )
    (net (code "229") (name "unconnected-(U2-UART0_RTS-Pad28)") (class "Default")
      (node (ref "U2") (pin "28") (pinfunction "UART0_RTS_28") (pintype "bidirectional"))
    )
    (net (code "230") (name "unconnected-(U2-UART2_CTS-Pad10)") (class "Default")
      (node (ref "U2") (pin "10") (pinfunction "UART2_CTS_10") (pintype "bidirectional"))
    )
    (net (code "231") (name "unconnected-(U2-UART2_RTS-Pad14)") (class "Default")
      (node (ref "U2") (pin "14") (pinfunction "UART2_RTS_14") (pintype "bidirectional"))
    )
    (net (code "232") (name "unconnected-(U2-UART2_RX-Pad13)") (class "Default")
      (node (ref "U2") (pin "13") (pinfunction "UART2_RX_13") (pintype "bidirectional"))
    )
    (net (code "233") (name "unconnected-(U2-UART2_TX-Pad16)") (class "Default")
      (node (ref "U2") (pin "16") (pinfunction "UART2_TX_16") (pintype "bidirectional"))
    )
    (net (code "234") (name "unconnected-(U2-USBO_DM-Pad51)") (class "Default")
      (node (ref "U2") (pin "51") (pinfunction "USBO_DM_51") (pintype "bidirectional"))
    )
    (net (code "235") (name "unconnected-(U2-USBO_DP-Pad52)") (class "Default")
      (node (ref "U2") (pin "52") (pinfunction "USBO_DP_52") (pintype "bidirectional"))
    )
    (net (code "236") (name "unconnected-(U2-VCC3VE-Pad41)") (class "Default")
      (node (ref "U2") (pin "41") (pinfunction "VCC3VE_41") (pintype "bidirectional"))
    )
    (net (code "237") (name "unconnected-(U2-VDDA_DAC_ADC-Pad7)") (class "Default")
      (node (ref "U2") (pin "7") (pinfunction "VDDA_DAC_ADC_7") (pintype "bidirectional"))
    )
    (net (code "238") (name "unconnected-(U3-TIMER1-Pad2)") (class "Default")
      (node (ref "U3") (pin "2") (pinfunction "TIMER1_2") (pintype "bidirectional"))
    )
    (net (code "239") (name "unconnected-(U3-TIMER2-Pad4)") (class "Default")
      (node (ref "U3") (pin "4") (pinfunction "TIMER2_4") (pintype "bidirectional"))
    )
    (net (code "240") (name "unconnected-(U3-TIMER3-Pad6)") (class "Default")
      (node (ref "U3") (pin "6") (pinfunction "TIMER3_6") (pintype "bidirectional"))
    )
    (net (code "241") (name "unconnected-(U3-TIMER4-Pad8)") (class "Default")
      (node (ref "U3") (pin "8") (pinfunction "TIMER4_8") (pintype "bidirectional"))
    )
    (net (code "242") (name "unconnected-(U4-TIMER1-Pad2)") (class "Default")
      (node (ref "U4") (pin "2") (pinfunction "TIMER1_2") (pintype "bidirectional"))
    )
    (net (code "243") (name "unconnected-(U4-TIMER2-Pad4)") (class "Default")
      (node (ref "U4") (pin "4") (pinfunction "TIMER2_4") (pintype "bidirectional"))
    )
    (net (code "244") (name "unconnected-(U4-TIMER3-Pad6)") (class "Default")
      (node (ref "U4") (pin "6") (pinfunction "TIMER3_6") (pintype "bidirectional"))
    )
    (net (code "245") (name "unconnected-(U4-TIMER4-Pad8)") (class "Default")
      (node (ref "U4") (pin "8") (pinfunction "TIMER4_8") (pintype "bidirectional"))
    )
  )
)
